# TeensyCtrlr.net
KiCad netlist of a schematic drawn in EAGLE
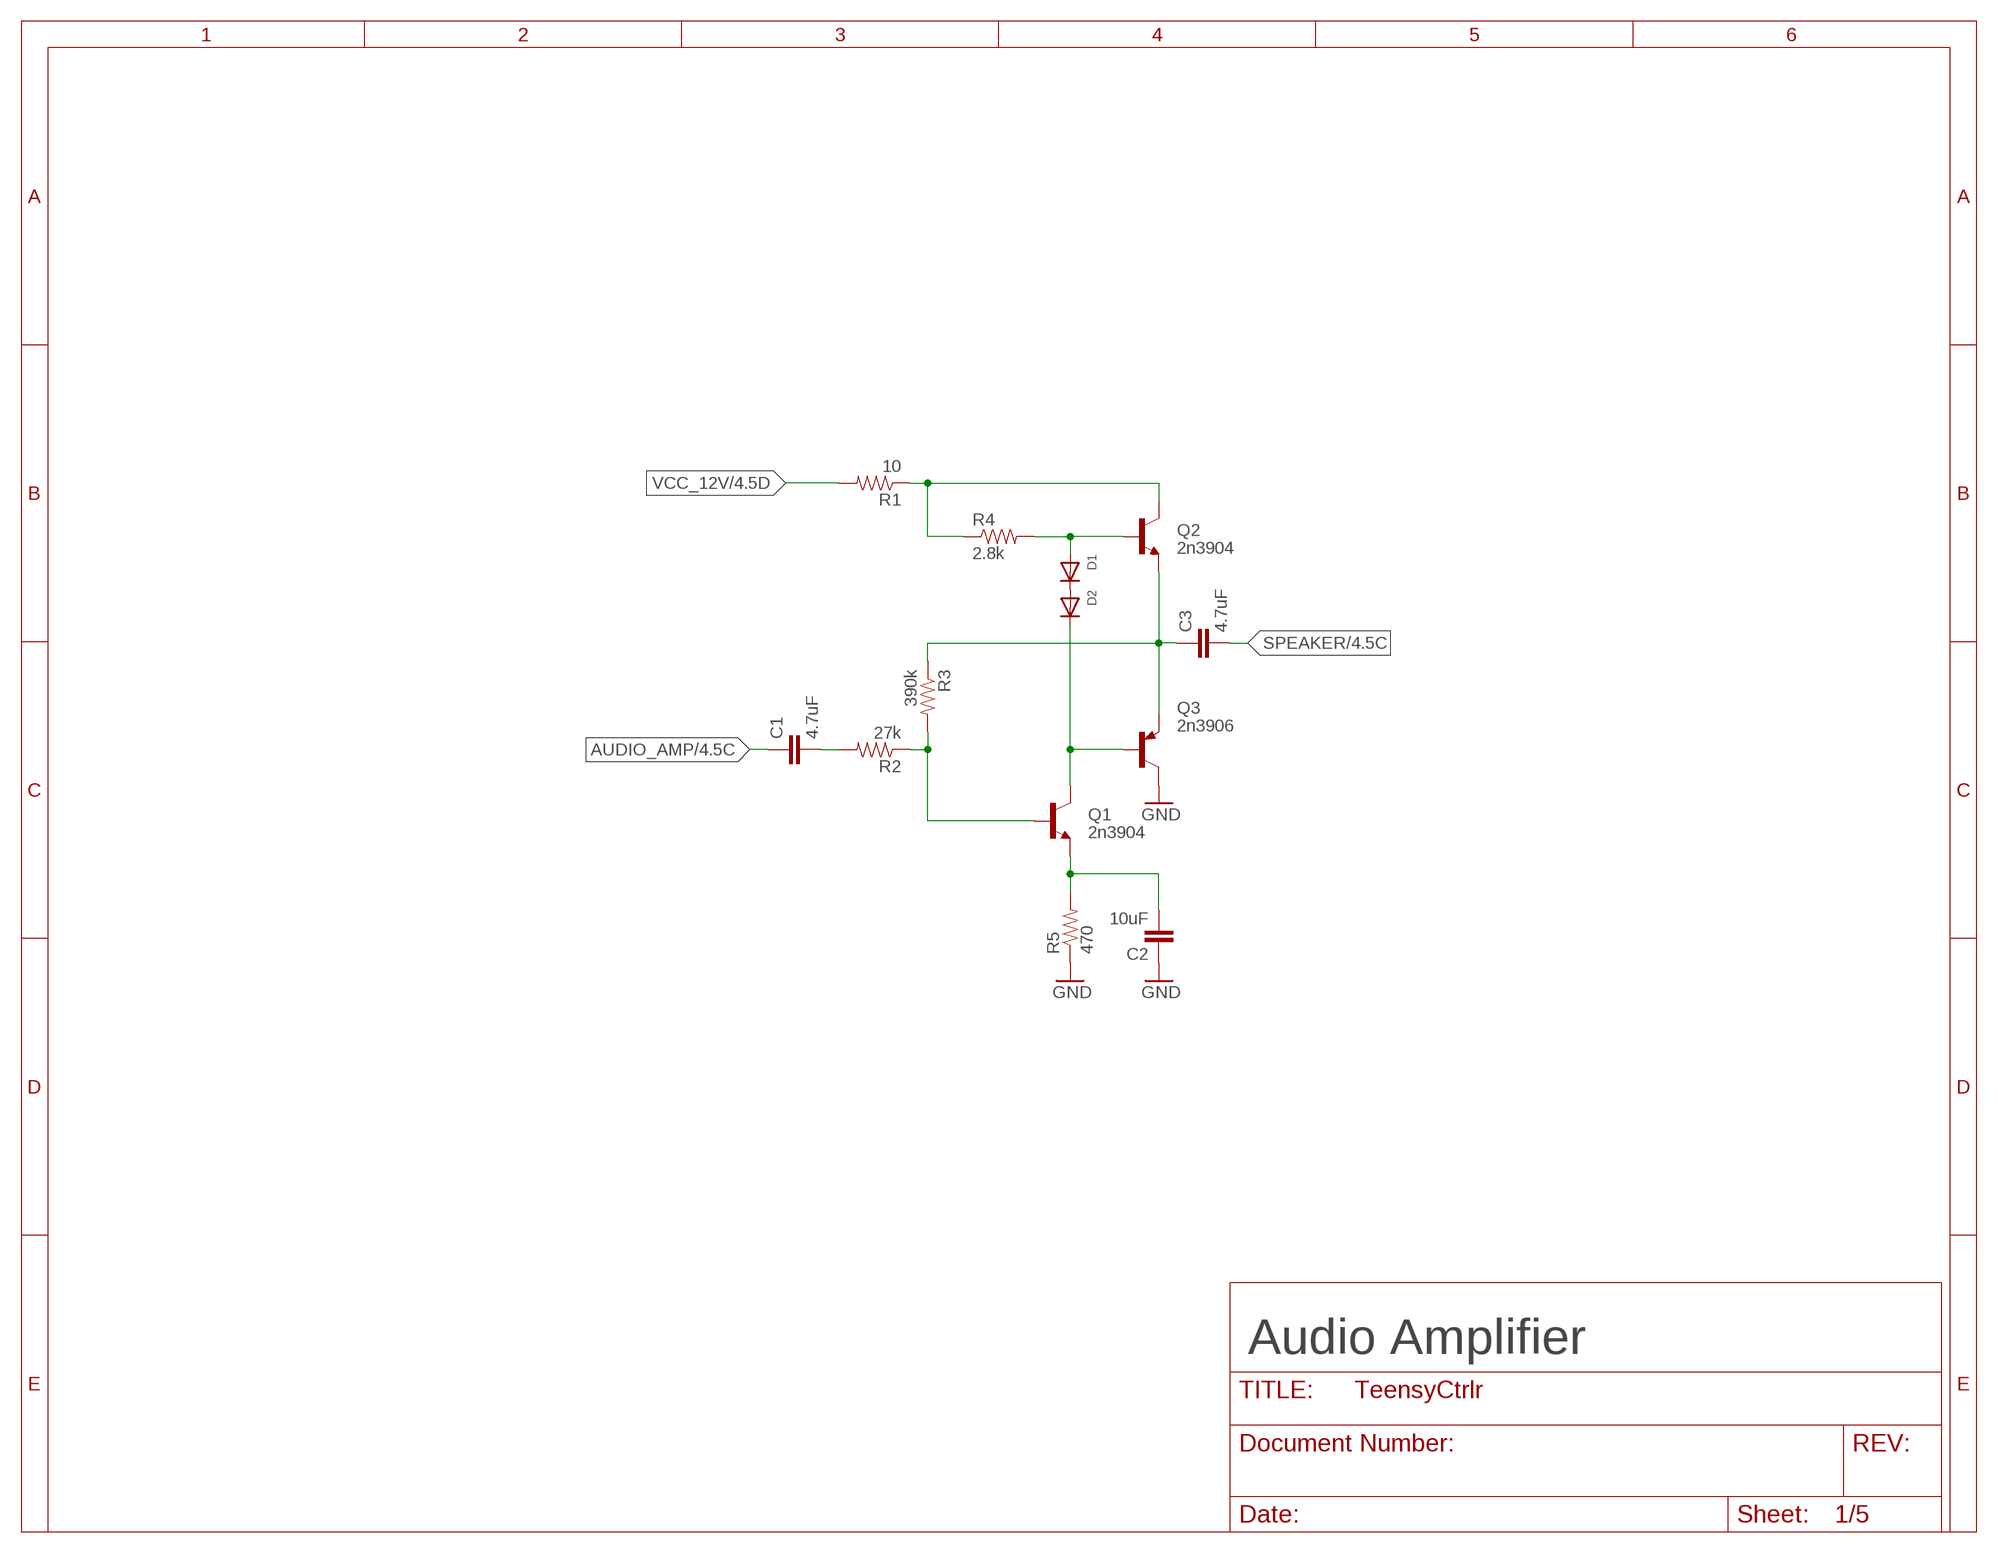
[diagram p0: schematic, sheet 1]
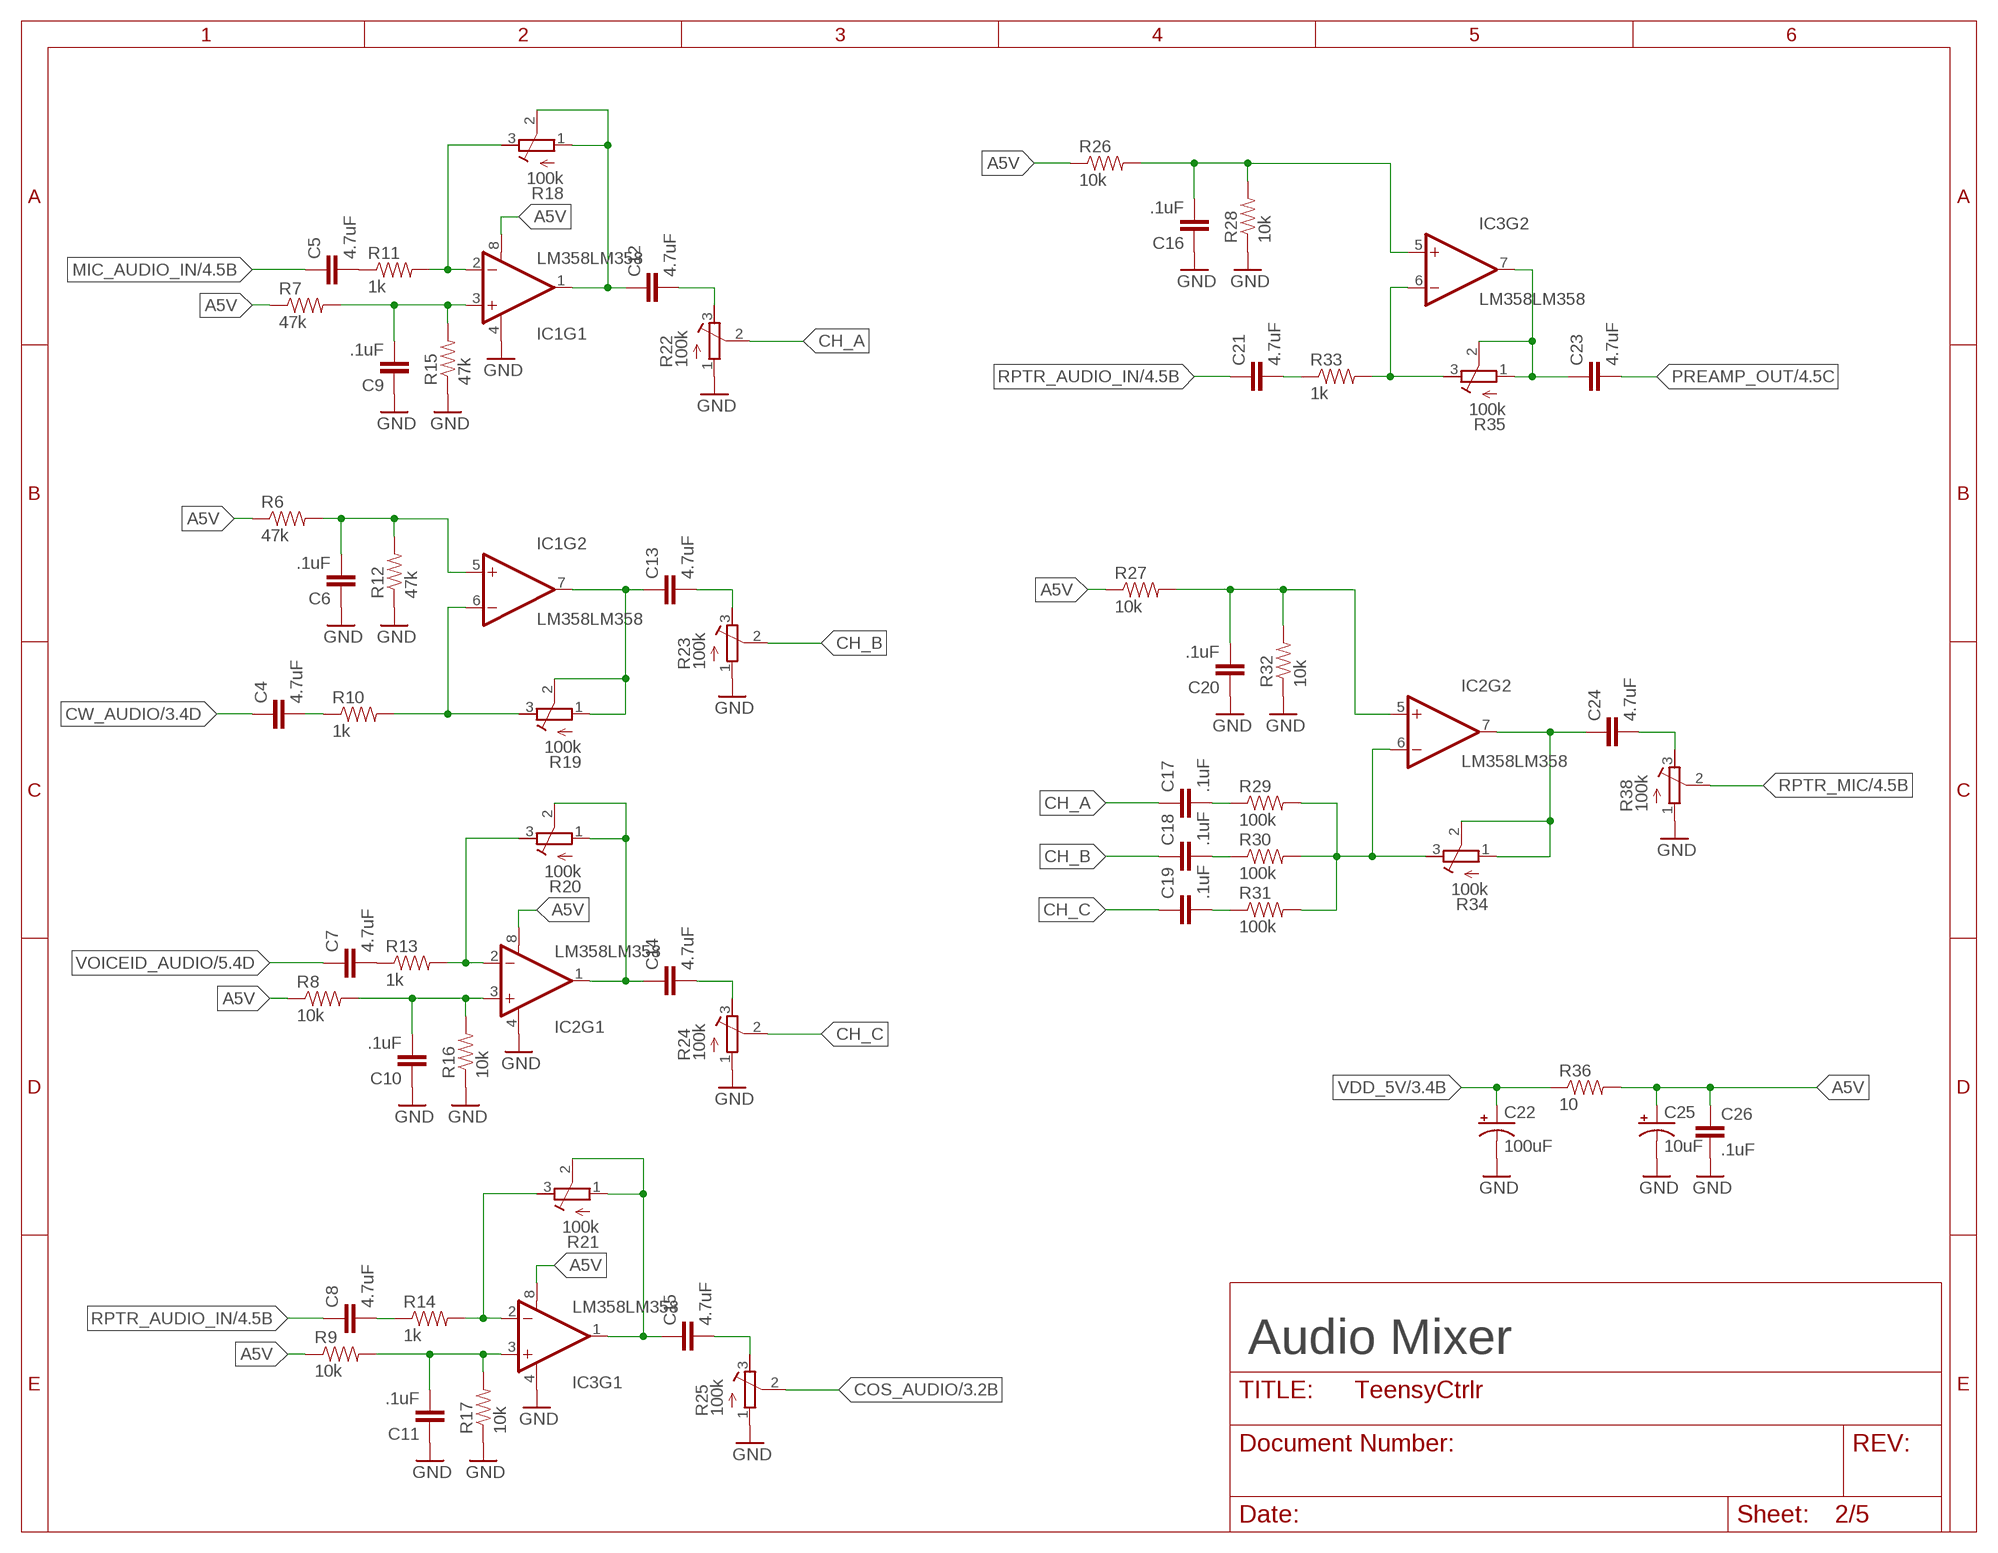
[diagram p1: schematic, sheet 2]
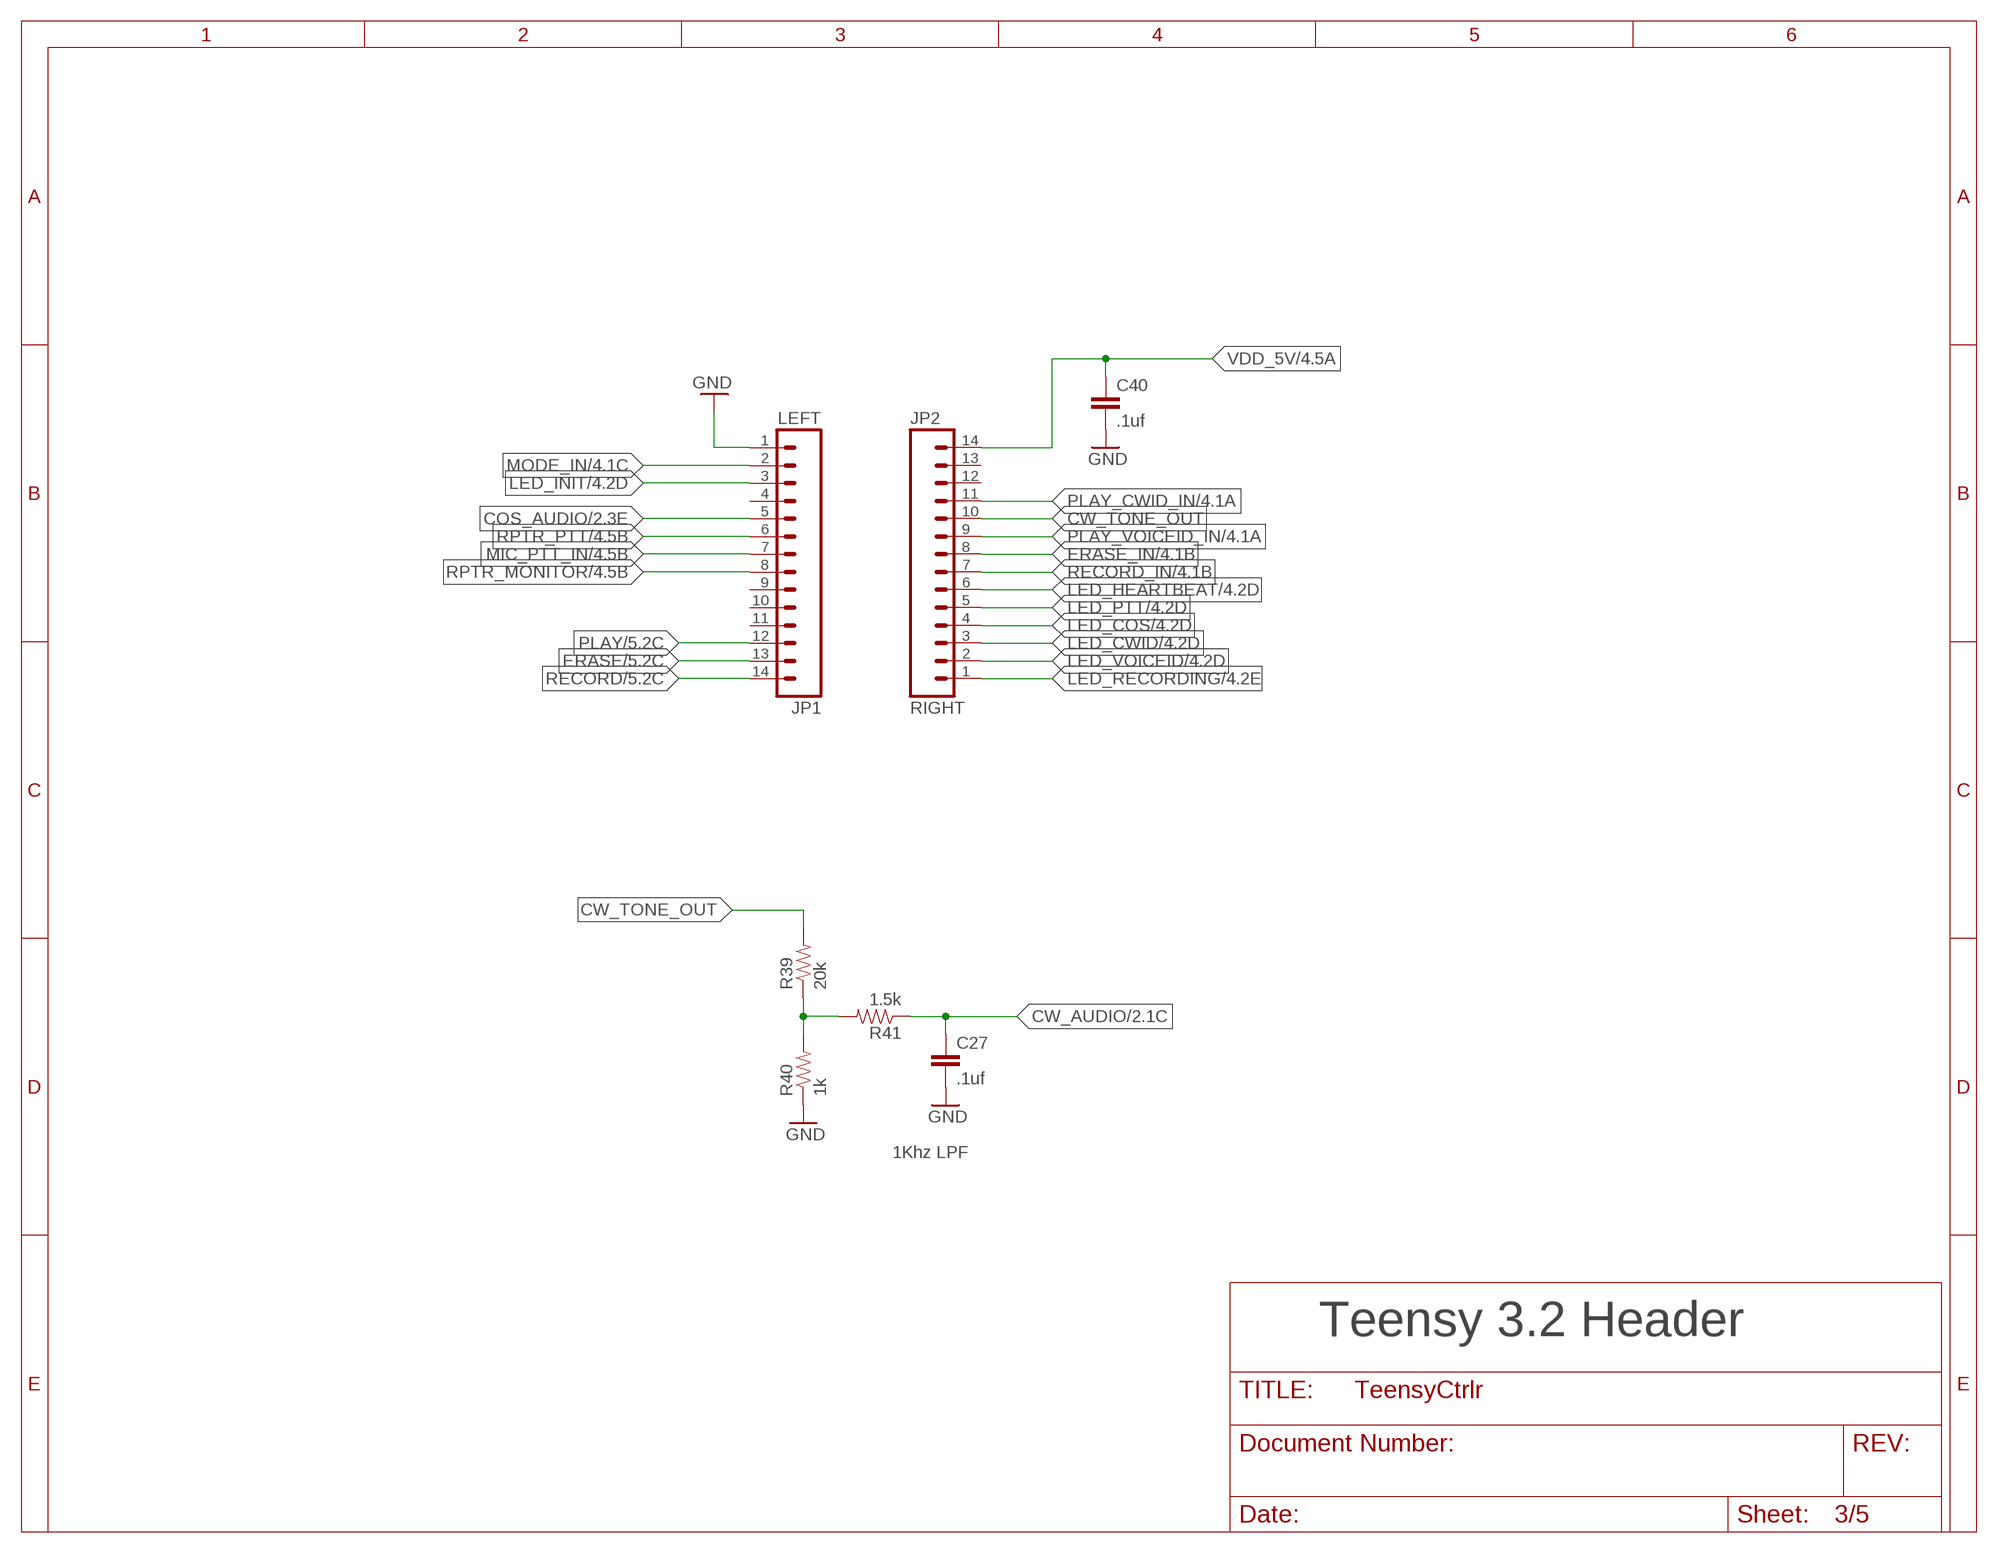
[diagram p2: schematic, sheet 3]
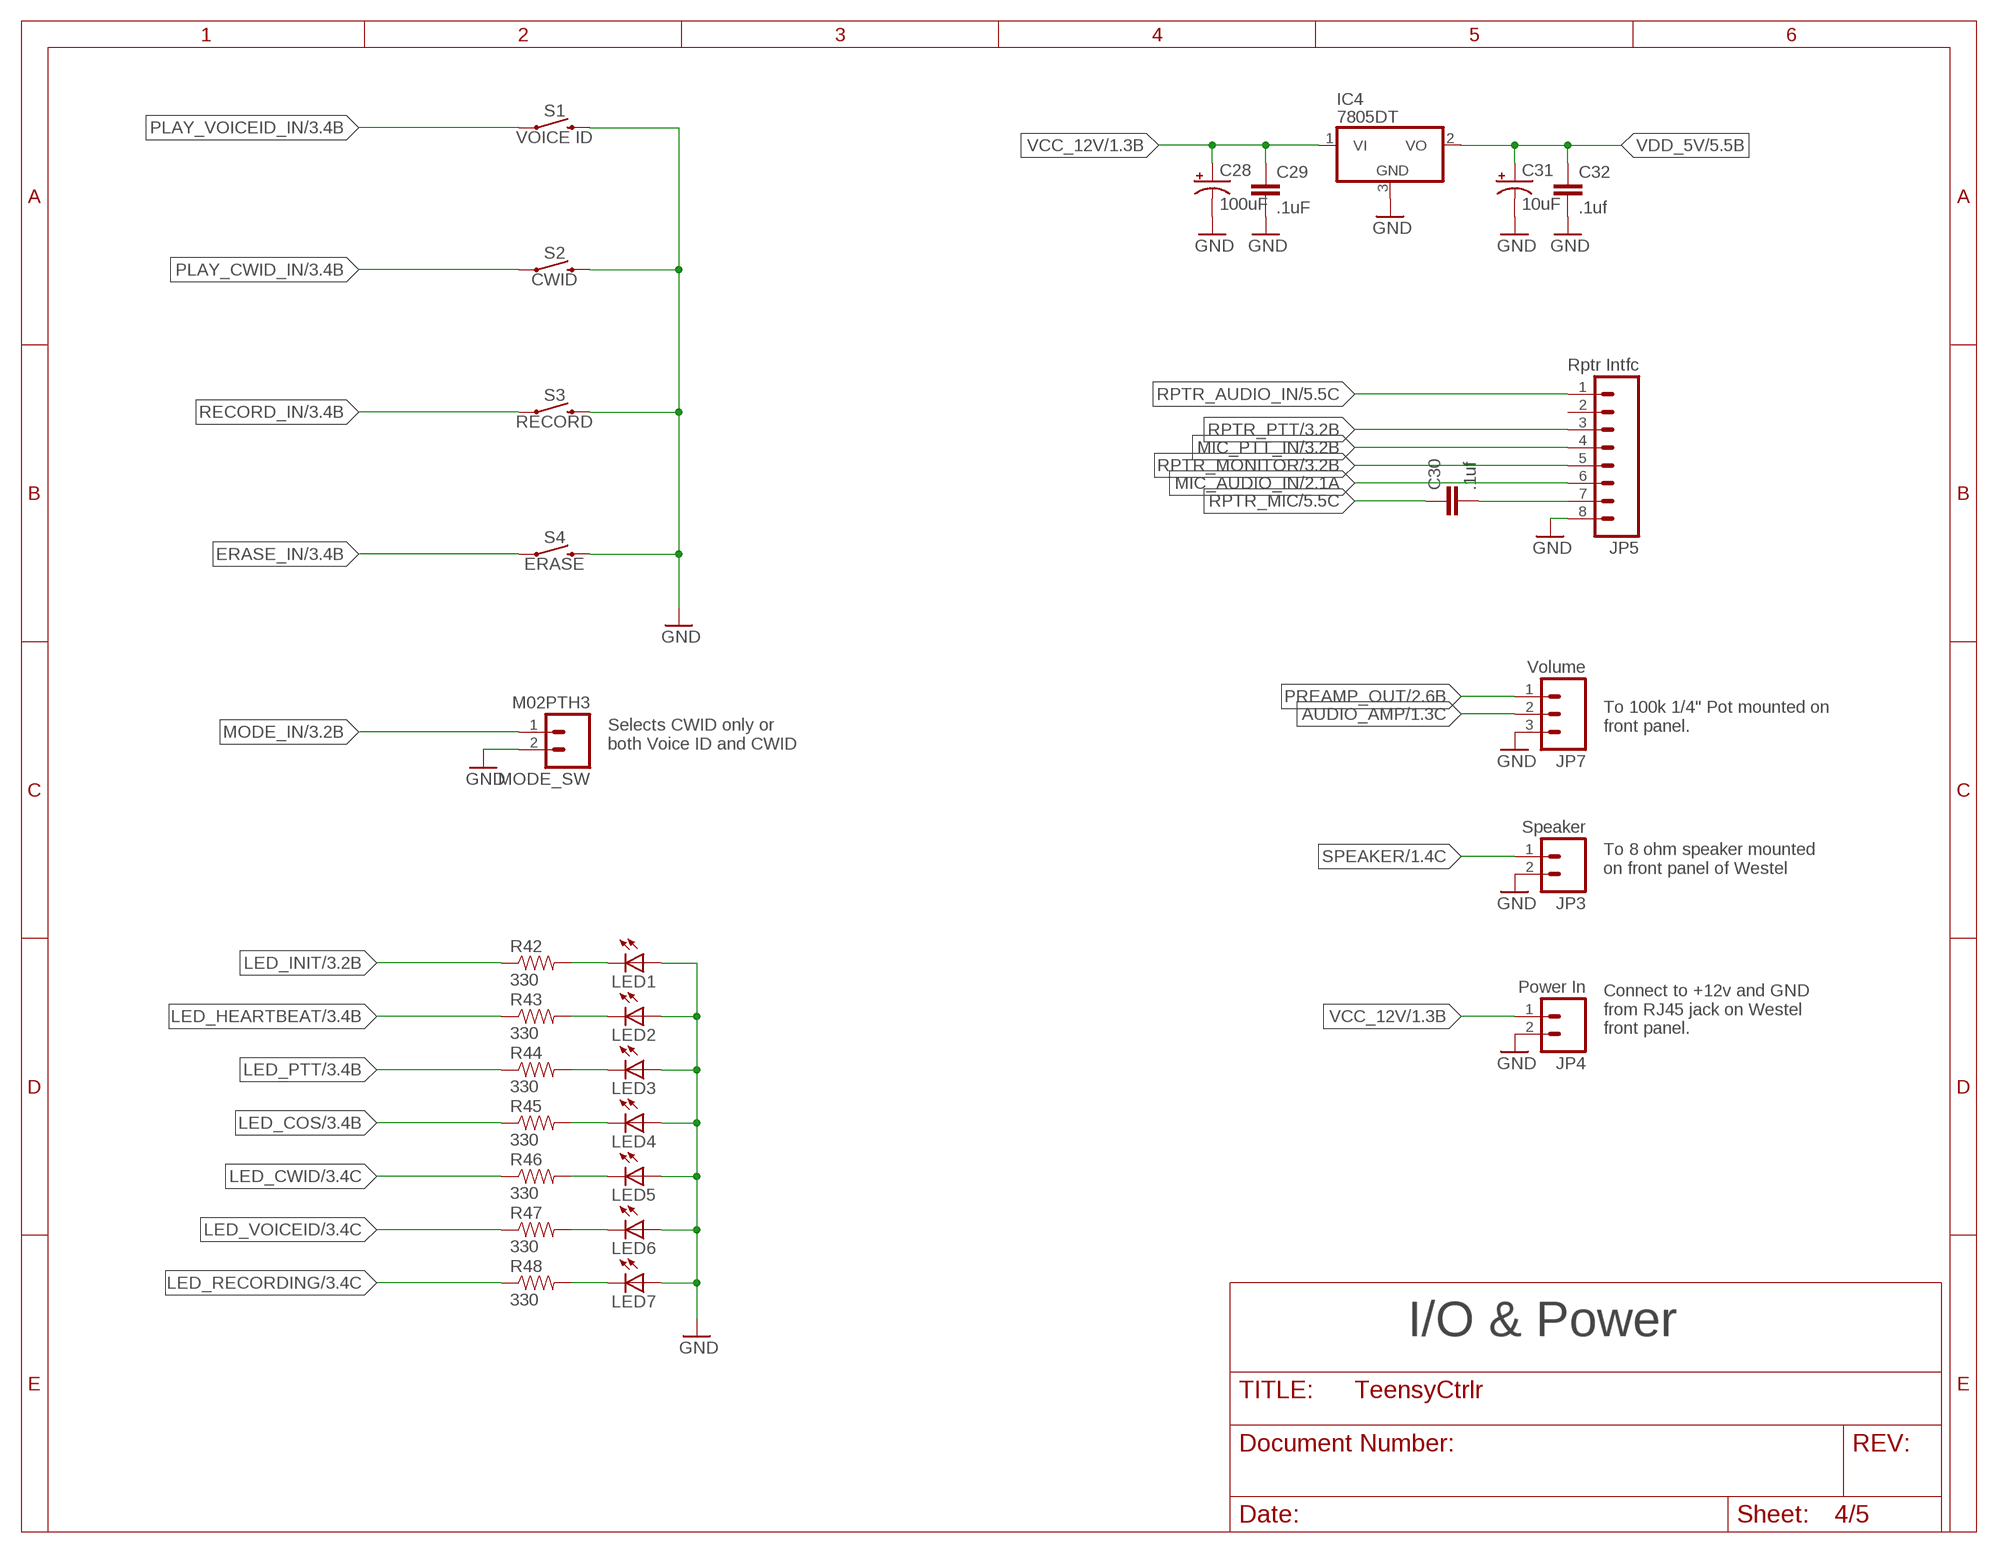
[diagram p3: schematic, sheet 4]
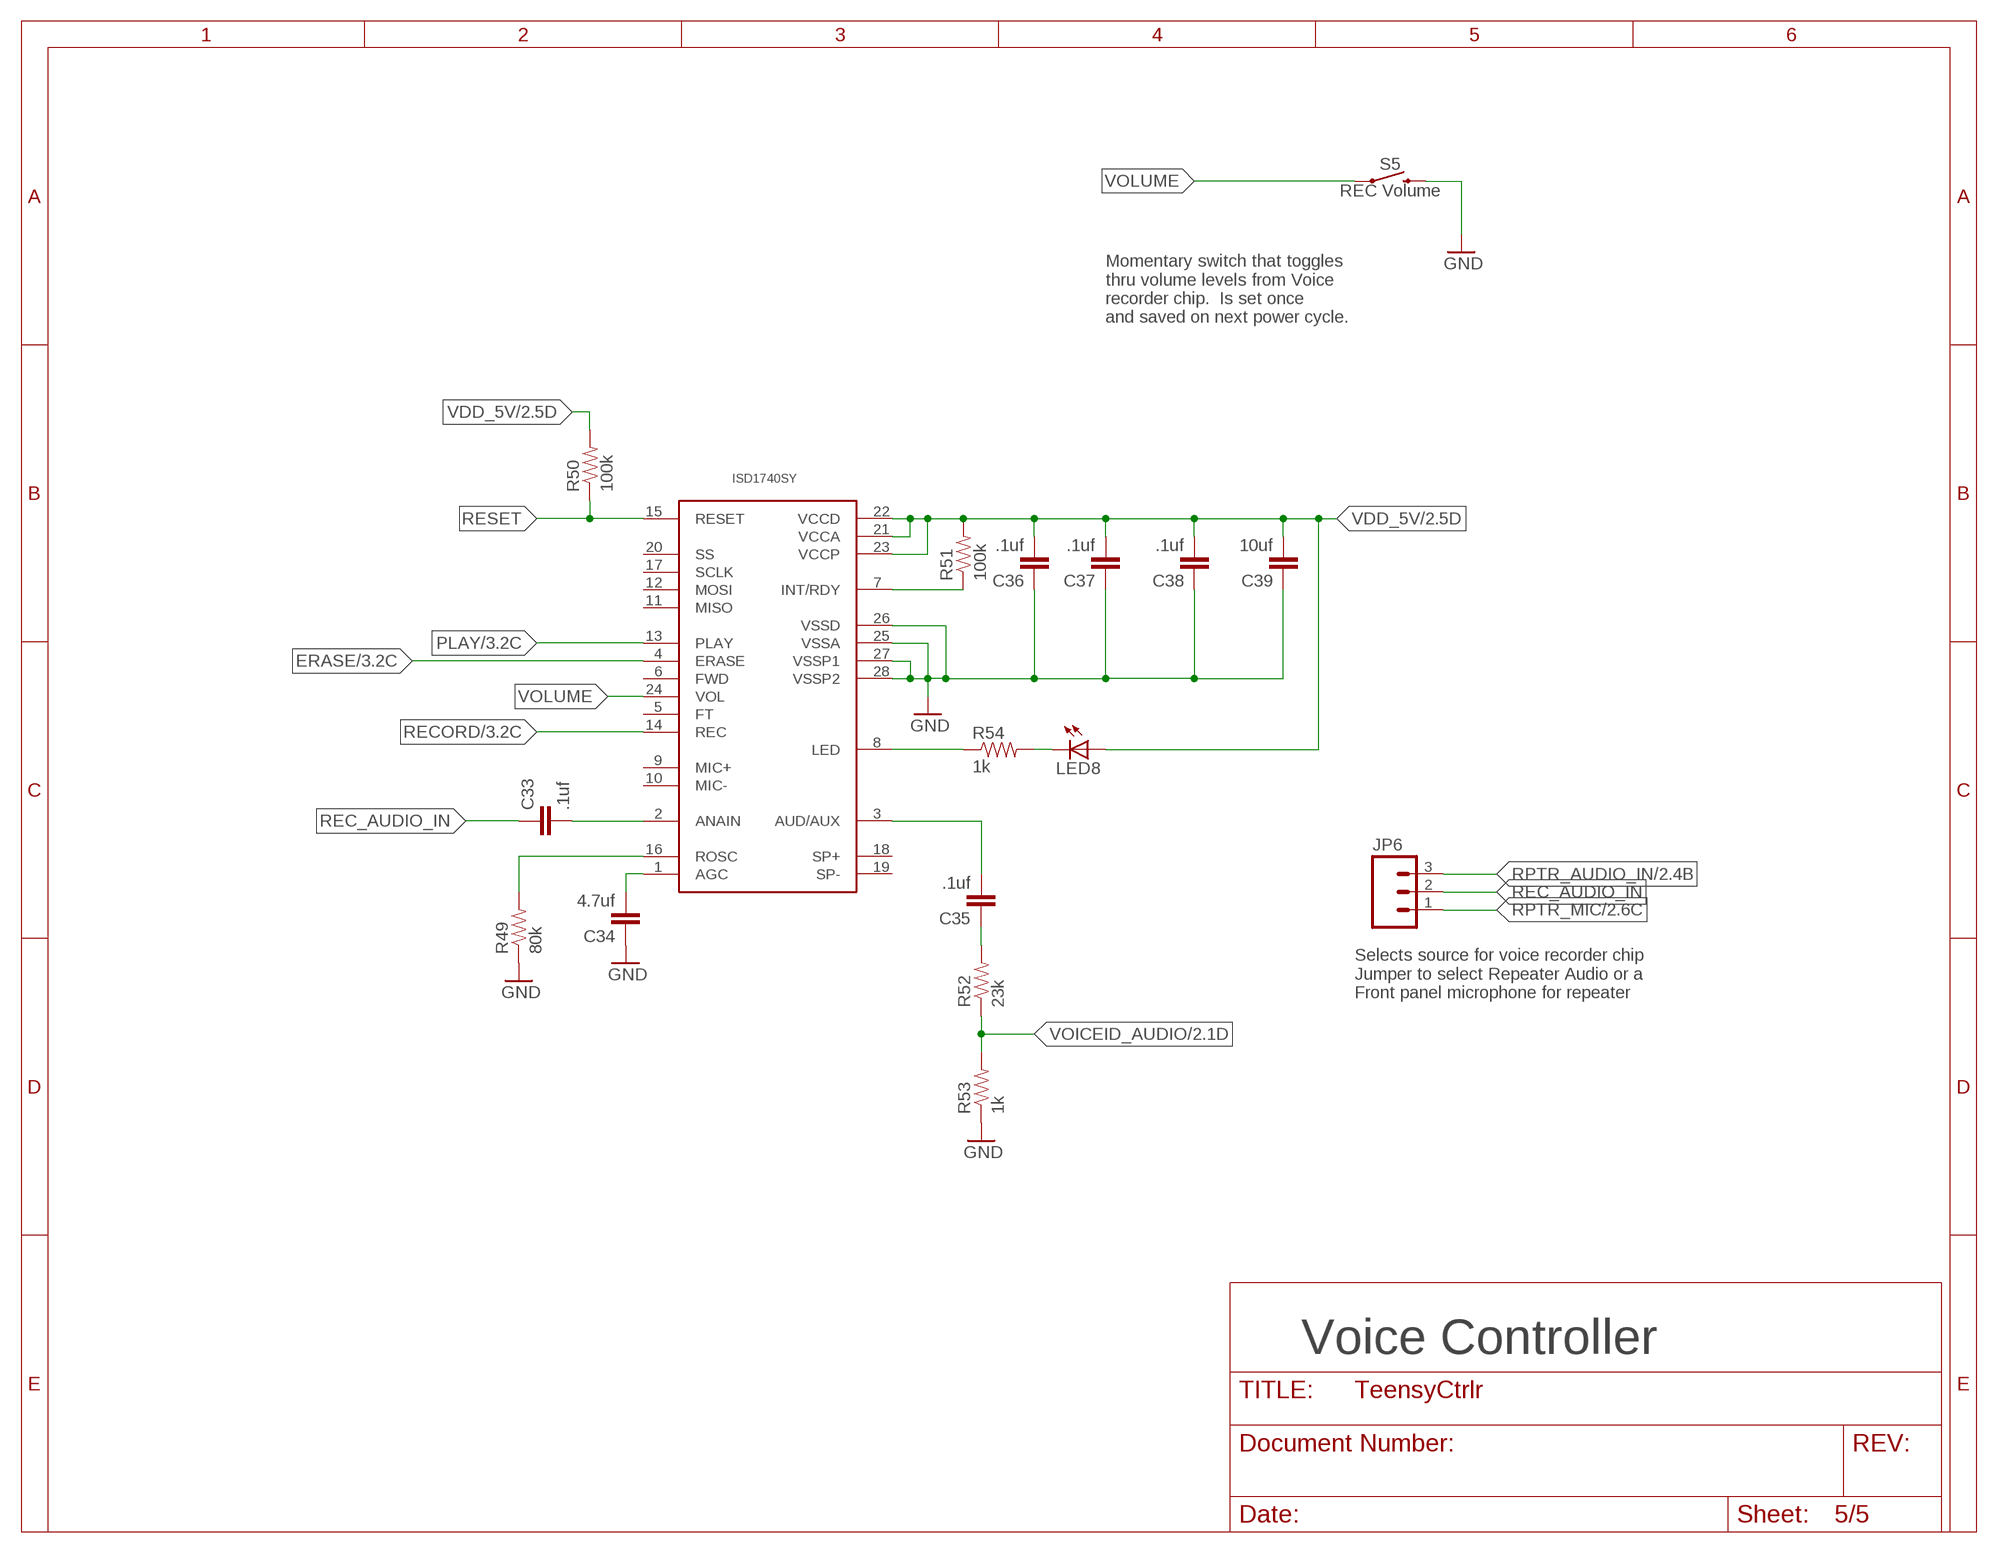
[diagram p4: schematic, sheet 5]

(export (version "E")
  (design (tool "Eeschema 10.0.6"))
  (components
    (comp (ref "C28")
      (value "100uF")
      (footprint "eagle-import:CPOL-RADIAL-1000UF-25V")
      (libsource (lib "eagle-import") (part "CAP_POLPTH4"))
    )
    (comp (ref "C29")
      (value ".1uF")
      (footprint "eagle-import:0805")
      (libsource (lib "eagle-import") (part "CAP0805"))
    )
    (comp (ref "C30")
      (value ".1uf")
      (footprint "eagle-import:0805")
      (libsource (lib "eagle-import") (part "CAP0805"))
    )
    (comp (ref "C31")
      (value "10uF")
      (footprint "eagle-import:CPOL-RADIAL-100UF-25V")
      (libsource (lib "eagle-import") (part "CAP_POLPTH1"))
    )
    (comp (ref "C32")
      (value ".1uf")
      (footprint "eagle-import:0805")
      (libsource (lib "eagle-import") (part "CAP0805"))
    )
    (comp (ref "IC4")
      (value "7805DT")
      (footprint "eagle-import:TO252")
      (libsource (lib "eagle-import") (part "78DT05"))
    )
    (comp (ref "JP3")
      (value "Speaker")
      (footprint "eagle-import:1X02_LONGPADS")
      (libsource (lib "eagle-import") (part "M02PTH3"))
    )
    (comp (ref "JP4")
      (value "Power In")
      (footprint "eagle-import:1X02_LONGPADS")
      (libsource (lib "eagle-import") (part "M02PTH3"))
    )
    (comp (ref "JP5")
      (value "Rptr Intfc")
      (footprint "eagle-import:1X08_LONGPADS")
      (libsource (lib "eagle-import") (part "M08LONGPADS"))
    )
    (comp (ref "JP7")
      (value "Volume")
      (footprint "eagle-import:1X03_LONGPADS")
      (libsource (lib "eagle-import") (part "M03LONGPADS"))
    )
    (comp (ref "LED1")
      (value "LED5MM")
      (footprint "eagle-import:LED5MM")
      (libsource (lib "eagle-import") (part "LED5MM"))
    )
    (comp (ref "LED2")
      (value "LED5MM")
      (footprint "eagle-import:LED5MM")
      (libsource (lib "eagle-import") (part "LED5MM"))
    )
    (comp (ref "LED3")
      (value "LED5MM")
      (footprint "eagle-import:LED5MM")
      (libsource (lib "eagle-import") (part "LED5MM"))
    )
    (comp (ref "LED4")
      (value "LED5MM")
      (footprint "eagle-import:LED5MM")
      (libsource (lib "eagle-import") (part "LED5MM"))
    )
    (comp (ref "LED5")
      (value "LED5MM")
      (footprint "eagle-import:LED5MM")
      (libsource (lib "eagle-import") (part "LED5MM"))
    )
    (comp (ref "LED6")
      (value "LED5MM")
      (footprint "eagle-import:LED5MM")
      (libsource (lib "eagle-import") (part "LED5MM"))
    )
    (comp (ref "LED7")
      (value "LED5MM")
      (footprint "eagle-import:LED5MM")
      (libsource (lib "eagle-import") (part "LED5MM"))
    )
    (comp (ref "MODE_SW")
      (value "M02PTH3")
      (footprint "eagle-import:1X02_LONGPADS")
      (libsource (lib "eagle-import") (part "M02PTH3"))
    )
    (comp (ref "R42")
      (value "330")
      (footprint "eagle-import:0805")
      (libsource (lib "eagle-import") (part "RESISTOR0805-RES"))
    )
    (comp (ref "R43")
      (value "330")
      (footprint "eagle-import:0805")
      (libsource (lib "eagle-import") (part "RESISTOR0805-RES"))
    )
    (comp (ref "R44")
      (value "330")
      (footprint "eagle-import:0805")
      (libsource (lib "eagle-import") (part "RESISTOR0805-RES"))
    )
    (comp (ref "R45")
      (value "330")
      (footprint "eagle-import:0805")
      (libsource (lib "eagle-import") (part "RESISTOR0805-RES"))
    )
    (comp (ref "R46")
      (value "330")
      (footprint "eagle-import:0805")
      (libsource (lib "eagle-import") (part "RESISTOR0805-RES"))
    )
    (comp (ref "R47")
      (value "330")
      (footprint "eagle-import:0805")
      (libsource (lib "eagle-import") (part "RESISTOR0805-RES"))
    )
    (comp (ref "R48")
      (value "330")
      (footprint "eagle-import:0805")
      (libsource (lib "eagle-import") (part "RESISTOR0805-RES"))
    )
    (comp (ref "S1")
      (value "VOICE ID")
      (footprint "eagle-import:TACTILE_SWITCH_PTH_6.0MM")
      (libsource (lib "eagle-import") (part "MOMENTARY-SWITCH-SPST-PTH-6.0MM"))
    )
    (comp (ref "S2")
      (value "CWID")
      (footprint "eagle-import:TACTILE_SWITCH_PTH_6.0MM")
      (libsource (lib "eagle-import") (part "MOMENTARY-SWITCH-SPST-PTH-6.0MM"))
    )
    (comp (ref "S3")
      (value "RECORD")
      (footprint "eagle-import:TACTILE_SWITCH_PTH_6.0MM")
      (libsource (lib "eagle-import") (part "MOMENTARY-SWITCH-SPST-PTH-6.0MM"))
    )
    (comp (ref "S4")
      (value "ERASE")
      (footprint "eagle-import:TACTILE_SWITCH_PTH_6.0MM")
      (libsource (lib "eagle-import") (part "MOMENTARY-SWITCH-SPST-PTH-6.0MM"))
    )
    (comp (ref "C1")
      (value "4.7uF")
      (footprint "eagle-import:CAP-PTH-SMALL")
      (libsource (lib "eagle-import") (part "CAPPTH"))
    )
    (comp (ref "C2")
      (value "10uF")
      (footprint "eagle-import:CAP-PTH-SMALL")
      (libsource (lib "eagle-import") (part "CAPPTH"))
    )
    (comp (ref "C3")
      (value "4.7uF")
      (footprint "eagle-import:CAP-PTH-SMALL")
      (libsource (lib "eagle-import") (part "CAPPTH"))
    )
    (comp (ref "D1")
      (value "DIODEDO-1N4148")
      (footprint "eagle-import:DO-1N4148")
      (libsource (lib "eagle-import") (part "DIODEDO-1N4148"))
    )
    (comp (ref "D2")
      (value "DIODEDO-1N4148")
      (footprint "eagle-import:DO-1N4148")
      (libsource (lib "eagle-import") (part "DIODEDO-1N4148"))
    )
    (comp (ref "Q1")
      (value "2n3904")
      (footprint "eagle-import:TO-92-AMMO")
      (libsource (lib "eagle-import") (part "TRANSISTOR_NPNTO-92-AMMO"))
    )
    (comp (ref "Q2")
      (value "2n3904")
      (footprint "eagle-import:TO-92-AMMO")
      (libsource (lib "eagle-import") (part "TRANSISTOR_NPNTO-92-AMMO"))
    )
    (comp (ref "Q3")
      (value "2n3906")
      (footprint "eagle-import:TO92-EBC")
      (libsource (lib "eagle-import") (part "-PNP-TO92-EBCBC328-25"))
    )
    (comp (ref "R1")
      (value "10")
      (footprint "eagle-import:0805")
      (libsource (lib "eagle-import") (part "RESISTOR0805-RES"))
    )
    (comp (ref "R2")
      (value "27k")
      (footprint "eagle-import:0805")
      (libsource (lib "eagle-import") (part "RESISTOR0805-RES"))
    )
    (comp (ref "R3")
      (value "390k")
      (footprint "eagle-import:0805")
      (libsource (lib "eagle-import") (part "RESISTOR0805-RES"))
    )
    (comp (ref "R4")
      (value "2.8k")
      (footprint "eagle-import:0805")
      (libsource (lib "eagle-import") (part "RESISTOR0805-RES"))
    )
    (comp (ref "R5")
      (value "470")
      (footprint "eagle-import:0805")
      (libsource (lib "eagle-import") (part "RESISTOR0805-RES"))
    )
    (comp (ref "C33")
      (value ".1uf")
      (footprint "eagle-import:0805")
      (libsource (lib "eagle-import") (part "CAP0805"))
    )
    (comp (ref "C34")
      (value "4.7uf")
      (footprint "eagle-import:0805")
      (libsource (lib "eagle-import") (part "CAP0805"))
    )
    (comp (ref "C35")
      (value ".1uf")
      (footprint "eagle-import:0805")
      (libsource (lib "eagle-import") (part "CAP0805"))
    )
    (comp (ref "C36")
      (value ".1uf")
      (footprint "eagle-import:0805")
      (libsource (lib "eagle-import") (part "CAP0805"))
    )
    (comp (ref "C37")
      (value ".1uf")
      (footprint "eagle-import:0805")
      (libsource (lib "eagle-import") (part "CAP0805"))
    )
    (comp (ref "C38")
      (value ".1uf")
      (footprint "eagle-import:0805")
      (libsource (lib "eagle-import") (part "CAP0805"))
    )
    (comp (ref "C39")
      (value "10uf")
      (footprint "eagle-import:0805")
      (libsource (lib "eagle-import") (part "CAP0805"))
    )
    (comp (ref "IC$1")
      (value "ISD1740SYSOIC28")
      (footprint "eagle-import:SOIC-28")
      (libsource (lib "eagle-import") (part "ISD1740SYSOIC28"))
    )
    (comp (ref "JP6")
      (value "M03LONGPADS")
      (footprint "eagle-import:1X03_LONGPADS")
      (libsource (lib "eagle-import") (part "M03LONGPADS"))
    )
    (comp (ref "LED8")
      (value "LEDCHIP-LED0805")
      (footprint "eagle-import:CHIP-LED0805")
      (libsource (lib "eagle-import") (part "LEDCHIP-LED0805"))
    )
    (comp (ref "R49")
      (value "80k")
      (footprint "eagle-import:0805")
      (libsource (lib "eagle-import") (part "RESISTOR0805-RES"))
    )
    (comp (ref "R50")
      (value "100k")
      (footprint "eagle-import:0805")
      (libsource (lib "eagle-import") (part "RESISTOR0805-RES"))
    )
    (comp (ref "R51")
      (value "100k")
      (footprint "eagle-import:0805")
      (libsource (lib "eagle-import") (part "RESISTOR0805-RES"))
    )
    (comp (ref "R52")
      (value "23k")
      (footprint "eagle-import:0805")
      (libsource (lib "eagle-import") (part "RESISTOR0805-RES"))
    )
    (comp (ref "R53")
      (value "1k")
      (footprint "eagle-import:0805")
      (libsource (lib "eagle-import") (part "RESISTOR0805-RES"))
    )
    (comp (ref "R54")
      (value "1k")
      (footprint "eagle-import:0805")
      (libsource (lib "eagle-import") (part "RESISTOR0805-RES"))
    )
    (comp (ref "S5")
      (value "REC Volume")
      (footprint "eagle-import:TACTILE_SWITCH_PTH_6.0MM")
      (libsource (lib "eagle-import") (part "MOMENTARY-SWITCH-SPST-PTH-6.0MM"))
    )
    (comp (ref "C27")
      (value ".1uf")
      (footprint "eagle-import:0805")
      (libsource (lib "eagle-import") (part "CAP0805"))
    )
    (comp (ref "C40")
      (value ".1uf")
      (footprint "eagle-import:0805")
      (libsource (lib "eagle-import") (part "CAP0805"))
    )
    (comp (ref "JP1")
      (value "LEFT")
      (footprint "eagle-import:1X14-LONGPADS")
      (libsource (lib "eagle-import") (part "M14LONGPADS"))
    )
    (comp (ref "JP2")
      (value "RIGHT")
      (footprint "eagle-import:1X14-LONGPADS")
      (libsource (lib "eagle-import") (part "M14LONGPADS"))
    )
    (comp (ref "R39")
      (value "20k")
      (footprint "eagle-import:0805")
      (libsource (lib "eagle-import") (part "RESISTOR0805-RES"))
    )
    (comp (ref "R40")
      (value "1k")
      (footprint "eagle-import:0805")
      (libsource (lib "eagle-import") (part "RESISTOR0805-RES"))
    )
    (comp (ref "R41")
      (value "1.5k")
      (footprint "eagle-import:0805")
      (libsource (lib "eagle-import") (part "RESISTOR0805-RES"))
    )
    (comp (ref "C4")
      (value "4.7uF")
      (footprint "eagle-import:CAP-PTH-SMALL2")
      (libsource (lib "eagle-import") (part "CAPPTH2"))
    )
    (comp (ref "C5")
      (value "4.7uF")
      (footprint "eagle-import:CAP-PTH-SMALL2")
      (libsource (lib "eagle-import") (part "CAPPTH2"))
    )
    (comp (ref "C6")
      (value ".1uF")
      (footprint "eagle-import:0805")
      (libsource (lib "eagle-import") (part "CAP0805"))
    )
    (comp (ref "C7")
      (value "4.7uF")
      (footprint "eagle-import:CAP-PTH-SMALL2")
      (libsource (lib "eagle-import") (part "CAPPTH2"))
    )
    (comp (ref "C8")
      (value "4.7uF")
      (footprint "eagle-import:CAP-PTH-SMALL2")
      (libsource (lib "eagle-import") (part "CAPPTH2"))
    )
    (comp (ref "C9")
      (value ".1uF")
      (footprint "eagle-import:0805")
      (libsource (lib "eagle-import") (part "CAP0805"))
    )
    (comp (ref "C10")
      (value ".1uF")
      (footprint "eagle-import:0805")
      (libsource (lib "eagle-import") (part "CAP0805"))
    )
    (comp (ref "C11")
      (value ".1uF")
      (footprint "eagle-import:0805")
      (libsource (lib "eagle-import") (part "CAP0805"))
    )
    (comp (ref "C12")
      (value "4.7uF")
      (footprint "eagle-import:CAP-PTH-SMALL2")
      (libsource (lib "eagle-import") (part "CAPPTH2"))
    )
    (comp (ref "C13")
      (value "4.7uF")
      (footprint "eagle-import:CAP-PTH-SMALL2")
      (libsource (lib "eagle-import") (part "CAPPTH2"))
    )
    (comp (ref "C14")
      (value "4.7uF")
      (footprint "eagle-import:CAP-PTH-SMALL2")
      (libsource (lib "eagle-import") (part "CAPPTH2"))
    )
    (comp (ref "C15")
      (value "4.7uF")
      (footprint "eagle-import:CAP-PTH-SMALL2")
      (libsource (lib "eagle-import") (part "CAPPTH2"))
    )
    (comp (ref "C16")
      (value ".1uF")
      (footprint "eagle-import:0805")
      (libsource (lib "eagle-import") (part "CAP0805"))
    )
    (comp (ref "C17")
      (value ".1uF")
      (footprint "eagle-import:0805")
      (libsource (lib "eagle-import") (part "CAP0805"))
    )
    (comp (ref "C18")
      (value ".1uF")
      (footprint "eagle-import:0805")
      (libsource (lib "eagle-import") (part "CAP0805"))
    )
    (comp (ref "C19")
      (value ".1uF")
      (footprint "eagle-import:0805")
      (libsource (lib "eagle-import") (part "CAP0805"))
    )
    (comp (ref "C20")
      (value ".1uF")
      (footprint "eagle-import:0805")
      (libsource (lib "eagle-import") (part "CAP0805"))
    )
    (comp (ref "C21")
      (value "4.7uF")
      (footprint "eagle-import:CAP-PTH-SMALL2")
      (libsource (lib "eagle-import") (part "CAPPTH2"))
    )
    (comp (ref "C22")
      (value "100uF")
      (footprint "eagle-import:CPOL-RADIAL-10UF-25V")
      (libsource (lib "eagle-import") (part "CAP_POLPTH2"))
    )
    (comp (ref "C23")
      (value "4.7uF")
      (footprint "eagle-import:CAP-PTH-SMALL2")
      (libsource (lib "eagle-import") (part "CAPPTH2"))
    )
    (comp (ref "C24")
      (value "4.7uF")
      (footprint "eagle-import:CAP-PTH-SMALL2")
      (libsource (lib "eagle-import") (part "CAPPTH2"))
    )
    (comp (ref "C25")
      (value "10uF")
      (footprint "eagle-import:CPOL-RADIAL-100UF-25V")
      (libsource (lib "eagle-import") (part "CAP_POLPTH1"))
    )
    (comp (ref "C26")
      (value ".1uF")
      (footprint "eagle-import:0805")
      (libsource (lib "eagle-import") (part "CAP0805"))
    )
    (comp (ref "IC1")
      (value "LM358LM358")
      (footprint "eagle-import:SOIC8")
      (libsource (lib "eagle-import") (part "LM358LM358"))
    )
    (comp (ref "IC2")
      (value "LM358LM358")
      (footprint "eagle-import:SOIC8")
      (libsource (lib "eagle-import") (part "LM358LM358"))
    )
    (comp (ref "IC3")
      (value "LM358LM358")
      (footprint "eagle-import:SOIC8")
      (libsource (lib "eagle-import") (part "LM358LM358"))
    )
    (comp (ref "R6")
      (value "47k")
      (footprint "eagle-import:0805")
      (libsource (lib "eagle-import") (part "RESISTOR0805-RES"))
    )
    (comp (ref "R7")
      (value "47k")
      (footprint "eagle-import:0805")
      (libsource (lib "eagle-import") (part "RESISTOR0805-RES"))
    )
    (comp (ref "R8")
      (value "10k")
      (footprint "eagle-import:0805")
      (libsource (lib "eagle-import") (part "RESISTOR0805-RES"))
    )
    (comp (ref "R9")
      (value "10k")
      (footprint "eagle-import:0805")
      (libsource (lib "eagle-import") (part "RESISTOR0805-RES"))
    )
    (comp (ref "R10")
      (value "1k")
      (footprint "eagle-import:0805")
      (libsource (lib "eagle-import") (part "RESISTOR0805-RES"))
    )
    (comp (ref "R11")
      (value "1k")
      (footprint "eagle-import:0805")
      (libsource (lib "eagle-import") (part "RESISTOR0805-RES"))
    )
    (comp (ref "R12")
      (value "47k")
      (footprint "eagle-import:0805")
      (libsource (lib "eagle-import") (part "RESISTOR0805-RES"))
    )
    (comp (ref "R13")
      (value "1k")
      (footprint "eagle-import:0805")
      (libsource (lib "eagle-import") (part "RESISTOR0805-RES"))
    )
    (comp (ref "R14")
      (value "1k")
      (footprint "eagle-import:0805")
      (libsource (lib "eagle-import") (part "RESISTOR0805-RES"))
    )
    (comp (ref "R15")
      (value "47k")
      (footprint "eagle-import:0805")
      (libsource (lib "eagle-import") (part "RESISTOR0805-RES"))
    )
    (comp (ref "R16")
      (value "10k")
      (footprint "eagle-import:0805")
      (libsource (lib "eagle-import") (part "RESISTOR0805-RES"))
    )
    (comp (ref "R17")
      (value "10k")
      (footprint "eagle-import:0805")
      (libsource (lib "eagle-import") (part "RESISTOR0805-RES"))
    )
    (comp (ref "R18")
      (value "100k")
      (footprint "eagle-import:RTRIM3296X")
      (libsource (lib "eagle-import") (part "R-TRIMM3296X"))
    )
    (comp (ref "R19")
      (value "100k")
      (footprint "eagle-import:RTRIM3296X")
      (libsource (lib "eagle-import") (part "R-TRIMM3296X"))
    )
    (comp (ref "R20")
      (value "100k")
      (footprint "eagle-import:RTRIM3296X")
      (libsource (lib "eagle-import") (part "R-TRIMM3296X"))
    )
    (comp (ref "R21")
      (value "100k")
      (footprint "eagle-import:RTRIM3296X")
      (libsource (lib "eagle-import") (part "R-TRIMM3296X"))
    )
    (comp (ref "R22")
      (value "100k")
      (footprint "eagle-import:RTRIM3296X")
      (libsource (lib "eagle-import") (part "R-TRIMM3296X"))
    )
    (comp (ref "R23")
      (value "100k")
      (footprint "eagle-import:RTRIM3296X")
      (libsource (lib "eagle-import") (part "R-TRIMM3296X"))
    )
    (comp (ref "R24")
      (value "100k")
      (footprint "eagle-import:RTRIM3296X")
      (libsource (lib "eagle-import") (part "R-TRIMM3296X"))
    )
    (comp (ref "R25")
      (value "100k")
      (footprint "eagle-import:RTRIM3296X")
      (libsource (lib "eagle-import") (part "R-TRIMM3296X"))
    )
    (comp (ref "R26")
      (value "10k")
      (footprint "eagle-import:0805")
      (libsource (lib "eagle-import") (part "RESISTOR0805-RES"))
    )
    (comp (ref "R27")
      (value "10k")
      (footprint "eagle-import:0805")
      (libsource (lib "eagle-import") (part "RESISTOR0805-RES"))
    )
    (comp (ref "R28")
      (value "10k")
      (footprint "eagle-import:0805")
      (libsource (lib "eagle-import") (part "RESISTOR0805-RES"))
    )
    (comp (ref "R29")
      (value "100k")
      (footprint "eagle-import:0805")
      (libsource (lib "eagle-import") (part "RESISTOR0805-RES"))
    )
    (comp (ref "R30")
      (value "100k")
      (footprint "eagle-import:0805")
      (libsource (lib "eagle-import") (part "RESISTOR0805-RES"))
    )
    (comp (ref "R31")
      (value "100k")
      (footprint "eagle-import:0805")
      (libsource (lib "eagle-import") (part "RESISTOR0805-RES"))
    )
    (comp (ref "R32")
      (value "10k")
      (footprint "eagle-import:0805")
      (libsource (lib "eagle-import") (part "RESISTOR0805-RES"))
    )
    (comp (ref "R33")
      (value "1k")
      (footprint "eagle-import:0805")
      (libsource (lib "eagle-import") (part "RESISTOR0805-RES"))
    )
    (comp (ref "R34")
      (value "100k")
      (footprint "eagle-import:RTRIM3296X")
      (libsource (lib "eagle-import") (part "R-TRIMM3296X"))
    )
    (comp (ref "R35")
      (value "100k")
      (footprint "eagle-import:RTRIM3296X")
      (libsource (lib "eagle-import") (part "R-TRIMM3296X"))
    )
    (comp (ref "R36")
      (value "10")
      (footprint "eagle-import:0805")
      (libsource (lib "eagle-import") (part "RESISTOR0805-RES"))
    )
    (comp (ref "R38")
      (value "100k")
      (footprint "eagle-import:RTRIM3296X")
      (libsource (lib "eagle-import") (part "R-TRIMM3296X"))
    )
  )
  (nets
    (net (code "1") (name "A5V") (class "Default")
      (node (ref "C25") (pin "1") (pinfunction "+_1") (pintype "passive"))
      (node (ref "C26") (pin "1") (pinfunction "1_1") (pintype "passive"))
      (node (ref "IC1") (pin "8") (pinfunction "V+_8") (pintype "power_in"))
      (node (ref "IC2") (pin "8") (pinfunction "V+_8") (pintype "power_in"))
      (node (ref "IC3") (pin "8") (pinfunction "V+_8") (pintype "power_in"))
      (node (ref "R26") (pin "1") (pinfunction "1_1") (pintype "passive"))
      (node (ref "R27") (pin "1") (pinfunction "1_1") (pintype "passive"))
      (node (ref "R36") (pin "2") (pinfunction "2_2") (pintype "passive"))
      (node (ref "R6") (pin "1") (pinfunction "1_1") (pintype "passive"))
      (node (ref "R7") (pin "1") (pinfunction "1_1") (pintype "passive"))
      (node (ref "R8") (pin "1") (pinfunction "1_1") (pintype "passive"))
      (node (ref "R9") (pin "1") (pinfunction "1_1") (pintype "passive"))
    )
    (net (code "2") (name "AUDIO_AMP") (class "Default")
      (node (ref "C1") (pin "1") (pinfunction "1_1") (pintype "passive"))
      (node (ref "JP7") (pin "2") (pinfunction "2_2") (pintype "passive"))
    )
    (net (code "3") (name "CH_A") (class "Default")
      (node (ref "C17") (pin "1") (pinfunction "1_1") (pintype "passive"))
      (node (ref "R22") (pin "2") (pinfunction "S_2") (pintype "passive"))
    )
    (net (code "4") (name "CH_B") (class "Default")
      (node (ref "C18") (pin "1") (pinfunction "1_1") (pintype "passive"))
      (node (ref "R23") (pin "2") (pinfunction "S_2") (pintype "passive"))
    )
    (net (code "5") (name "CH_C") (class "Default")
      (node (ref "C19") (pin "1") (pinfunction "1_1") (pintype "passive"))
      (node (ref "R24") (pin "2") (pinfunction "S_2") (pintype "passive"))
    )
    (net (code "6") (name "COS_AUDIO") (class "Default")
      (node (ref "JP1") (pin "5") (pinfunction "5_5") (pintype "passive"))
      (node (ref "R25") (pin "2") (pinfunction "S_2") (pintype "passive"))
    )
    (net (code "7") (name "CW_AUDIO") (class "Default")
      (node (ref "C27") (pin "1") (pinfunction "1_1") (pintype "passive"))
      (node (ref "C4") (pin "1") (pinfunction "1_1") (pintype "passive"))
      (node (ref "R41") (pin "1") (pinfunction "1_1") (pintype "passive"))
    )
    (net (code "8") (name "CW_TONE_OUT") (class "Default")
      (node (ref "JP2") (pin "10") (pinfunction "10_10") (pintype "passive"))
      (node (ref "R39") (pin "2") (pinfunction "2_2") (pintype "passive"))
    )
    (net (code "9") (name "ERASE") (class "Default")
      (node (ref "IC$1") (pin "4") (pinfunction "ERASE_4") (pintype "bidirectional"))
      (node (ref "JP1") (pin "13") (pinfunction "13_13") (pintype "passive"))
    )
    (net (code "10") (name "ERASE_IN") (class "Default")
      (node (ref "JP2") (pin "8") (pinfunction "8_8") (pintype "passive"))
      (node (ref "S4") (pin "1") (pinfunction "1_1") (pintype "passive"))
    )
    (net (code "11") (name "GND") (class "Default")
      (node (ref "C10") (pin "1") (pinfunction "1_1") (pintype "passive"))
      (node (ref "C11") (pin "1") (pinfunction "1_1") (pintype "passive"))
      (node (ref "C16") (pin "1") (pinfunction "1_1") (pintype "passive"))
      (node (ref "C2") (pin "1") (pinfunction "1_1") (pintype "passive"))
      (node (ref "C20") (pin "1") (pinfunction "1_1") (pintype "passive"))
      (node (ref "C22") (pin "2") (pinfunction "-_2") (pintype "passive"))
      (node (ref "C25") (pin "2") (pinfunction "-_2") (pintype "passive"))
      (node (ref "C26") (pin "2") (pinfunction "2_2") (pintype "passive"))
      (node (ref "C27") (pin "2") (pinfunction "2_2") (pintype "passive"))
      (node (ref "C28") (pin "-") (pinfunction "-_-") (pintype "passive"))
      (node (ref "C29") (pin "2") (pinfunction "2_2") (pintype "passive"))
      (node (ref "C31") (pin "2") (pinfunction "-_2") (pintype "passive"))
      (node (ref "C32") (pin "2") (pinfunction "2_2") (pintype "passive"))
      (node (ref "C34") (pin "1") (pinfunction "1_1") (pintype "passive"))
      (node (ref "C36") (pin "1") (pinfunction "1_1") (pintype "passive"))
      (node (ref "C37") (pin "1") (pinfunction "1_1") (pintype "passive"))
      (node (ref "C38") (pin "1") (pinfunction "1_1") (pintype "passive"))
      (node (ref "C39") (pin "1") (pinfunction "1_1") (pintype "passive"))
      (node (ref "C40") (pin "2") (pinfunction "2_2") (pintype "passive"))
      (node (ref "C6") (pin "1") (pinfunction "1_1") (pintype "passive"))
      (node (ref "C9") (pin "1") (pinfunction "1_1") (pintype "passive"))
      (node (ref "IC$1") (pin "25") (pinfunction "VSSA_25") (pintype "bidirectional"))
      (node (ref "IC$1") (pin "26") (pinfunction "VSSD_26") (pintype "bidirectional"))
      (node (ref "IC$1") (pin "27") (pinfunction "VSSP1_27") (pintype "bidirectional"))
      (node (ref "IC$1") (pin "28") (pinfunction "VSSP2_28") (pintype "bidirectional"))
      (node (ref "IC1") (pin "4") (pinfunction "V-_4") (pintype "power_in"))
      (node (ref "IC2") (pin "4") (pinfunction "V-_4") (pintype "power_in"))
      (node (ref "IC3") (pin "4") (pinfunction "V-_4") (pintype "power_in"))
      (node (ref "IC4") (pin "3") (pinfunction "GND_3") (pintype "passive"))
      (node (ref "JP1") (pin "1") (pinfunction "1_1") (pintype "passive"))
      (node (ref "JP3") (pin "2") (pinfunction "2_2") (pintype "passive"))
      (node (ref "JP4") (pin "2") (pinfunction "2_2") (pintype "passive"))
      (node (ref "JP5") (pin "8") (pinfunction "8_8") (pintype "passive"))
      (node (ref "JP7") (pin "3") (pinfunction "3_3") (pintype "passive"))
      (node (ref "LED1") (pin "A") (pinfunction "A_A") (pintype "passive"))
      (node (ref "LED2") (pin "A") (pinfunction "A_A") (pintype "passive"))
      (node (ref "LED3") (pin "A") (pinfunction "A_A") (pintype "passive"))
      (node (ref "LED4") (pin "A") (pinfunction "A_A") (pintype "passive"))
      (node (ref "LED5") (pin "A") (pinfunction "A_A") (pintype "passive"))
      (node (ref "LED6") (pin "A") (pinfunction "A_A") (pintype "passive"))
      (node (ref "LED7") (pin "A") (pinfunction "A_A") (pintype "passive"))
      (node (ref "MODE_SW") (pin "2") (pinfunction "2_2") (pintype "passive"))
      (node (ref "Q3") (pin "C") (pinfunction "C_C") (pintype "passive"))
      (node (ref "R12") (pin "1") (pinfunction "1_1") (pintype "passive"))
      (node (ref "R15") (pin "1") (pinfunction "1_1") (pintype "passive"))
      (node (ref "R16") (pin "1") (pinfunction "1_1") (pintype "passive"))
      (node (ref "R17") (pin "1") (pinfunction "1_1") (pintype "passive"))
      (node (ref "R22") (pin "1") (pinfunction "A_1") (pintype "passive"))
      (node (ref "R23") (pin "1") (pinfunction "A_1") (pintype "passive"))
      (node (ref "R24") (pin "1") (pinfunction "A_1") (pintype "passive"))
      (node (ref "R25") (pin "1") (pinfunction "A_1") (pintype "passive"))
      (node (ref "R28") (pin "1") (pinfunction "1_1") (pintype "passive"))
      (node (ref "R32") (pin "1") (pinfunction "1_1") (pintype "passive"))
      (node (ref "R38") (pin "1") (pinfunction "A_1") (pintype "passive"))
      (node (ref "R40") (pin "1") (pinfunction "1_1") (pintype "passive"))
      (node (ref "R49") (pin "1") (pinfunction "1_1") (pintype "passive"))
      (node (ref "R5") (pin "1") (pinfunction "1_1") (pintype "passive"))
      (node (ref "R53") (pin "1") (pinfunction "1_1") (pintype "passive"))
      (node (ref "S1") (pin "3") (pinfunction "2_3") (pintype "passive"))
      (node (ref "S2") (pin "3") (pinfunction "2_3") (pintype "passive"))
      (node (ref "S3") (pin "3") (pinfunction "2_3") (pintype "passive"))
      (node (ref "S4") (pin "3") (pinfunction "2_3") (pintype "passive"))
      (node (ref "S5") (pin "3") (pinfunction "2_3") (pintype "passive"))
    )
    (net (code "12") (name "LED_COS") (class "Default")
      (node (ref "JP2") (pin "4") (pinfunction "4_4") (pintype "passive"))
      (node (ref "R45") (pin "1") (pinfunction "1_1") (pintype "passive"))
    )
    (net (code "13") (name "LED_CWID") (class "Default")
      (node (ref "JP2") (pin "3") (pinfunction "3_3") (pintype "passive"))
      (node (ref "R46") (pin "1") (pinfunction "1_1") (pintype "passive"))
    )
    (net (code "14") (name "LED_HEARTBEAT") (class "Default")
      (node (ref "JP2") (pin "6") (pinfunction "6_6") (pintype "passive"))
      (node (ref "R43") (pin "1") (pinfunction "1_1") (pintype "passive"))
    )
    (net (code "15") (name "LED_INIT") (class "Default")
      (node (ref "JP1") (pin "3") (pinfunction "3_3") (pintype "passive"))
      (node (ref "R42") (pin "1") (pinfunction "1_1") (pintype "passive"))
    )
    (net (code "16") (name "LED_PTT") (class "Default")
      (node (ref "JP2") (pin "5") (pinfunction "5_5") (pintype "passive"))
      (node (ref "R44") (pin "1") (pinfunction "1_1") (pintype "passive"))
    )
    (net (code "17") (name "LED_RECORDING") (class "Default")
      (node (ref "JP2") (pin "1") (pinfunction "1_1") (pintype "passive"))
      (node (ref "R48") (pin "1") (pinfunction "1_1") (pintype "passive"))
    )
    (net (code "18") (name "LED_VOICEID") (class "Default")
      (node (ref "JP2") (pin "2") (pinfunction "2_2") (pintype "passive"))
      (node (ref "R47") (pin "1") (pinfunction "1_1") (pintype "passive"))
    )
    (net (code "19") (name "MIC_AUDIO_IN") (class "Default")
      (node (ref "C5") (pin "1") (pinfunction "1_1") (pintype "passive"))
      (node (ref "JP5") (pin "6") (pinfunction "6_6") (pintype "passive"))
    )
    (net (code "20") (name "MIC_PTT_IN") (class "Default")
      (node (ref "JP1") (pin "7") (pinfunction "7_7") (pintype "passive"))
      (node (ref "JP5") (pin "4") (pinfunction "4_4") (pintype "passive"))
    )
    (net (code "21") (name "MODE_IN") (class "Default")
      (node (ref "JP1") (pin "2") (pinfunction "2_2") (pintype "passive"))
      (node (ref "MODE_SW") (pin "1") (pinfunction "1_1") (pintype "passive"))
    )
    (net (code "22") (name "Net-(C1-Pad2)") (class "Default")
      (node (ref "C1") (pin "2") (pinfunction "2_2") (pintype "passive"))
      (node (ref "R2") (pin "2") (pinfunction "2_2") (pintype "passive"))
    )
    (net (code "23") (name "Net-(C4-Pad2)") (class "Default")
      (node (ref "C4") (pin "2") (pinfunction "2_2") (pintype "passive"))
      (node (ref "R10") (pin "1") (pinfunction "1_1") (pintype "passive"))
    )
    (net (code "24") (name "Net-(C5-Pad2)") (class "Default")
      (node (ref "C5") (pin "2") (pinfunction "2_2") (pintype "passive"))
      (node (ref "R11") (pin "1") (pinfunction "1_1") (pintype "passive"))
    )
    (net (code "25") (name "Net-(C7-Pad2)") (class "Default")
      (node (ref "C7") (pin "2") (pinfunction "2_2") (pintype "passive"))
      (node (ref "R13") (pin "1") (pinfunction "1_1") (pintype "passive"))
    )
    (net (code "26") (name "Net-(C8-Pad2)") (class "Default")
      (node (ref "C8") (pin "2") (pinfunction "2_2") (pintype "passive"))
      (node (ref "R14") (pin "1") (pinfunction "1_1") (pintype "passive"))
    )
    (net (code "27") (name "Net-(C17-Pad2)") (class "Default")
      (node (ref "C17") (pin "2") (pinfunction "2_2") (pintype "passive"))
      (node (ref "R29") (pin "1") (pinfunction "1_1") (pintype "passive"))
    )
    (net (code "28") (name "Net-(C18-Pad2)") (class "Default")
      (node (ref "C18") (pin "2") (pinfunction "2_2") (pintype "passive"))
      (node (ref "R30") (pin "1") (pinfunction "1_1") (pintype "passive"))
    )
    (net (code "29") (name "Net-(C19-Pad2)") (class "Default")
      (node (ref "C19") (pin "2") (pinfunction "2_2") (pintype "passive"))
      (node (ref "R31") (pin "1") (pinfunction "1_1") (pintype "passive"))
    )
    (net (code "30") (name "Net-(C21-Pad2)") (class "Default")
      (node (ref "C21") (pin "2") (pinfunction "2_2") (pintype "passive"))
      (node (ref "R33") (pin "1") (pinfunction "1_1") (pintype "passive"))
    )
    (net (code "31") (name "Net-(C30-Pad2)") (class "Default")
      (node (ref "C30") (pin "2") (pinfunction "2_2") (pintype "passive"))
      (node (ref "JP5") (pin "7") (pinfunction "7_7") (pintype "passive"))
    )
    (net (code "32") (name "Net-(C35-Pad1)") (class "Default")
      (node (ref "C35") (pin "1") (pinfunction "1_1") (pintype "passive"))
      (node (ref "R52") (pin "2") (pinfunction "2_2") (pintype "passive"))
    )
    (net (code "33") (name "Net-(D1-PadC)") (class "Default")
      (node (ref "D1") (pin "C") (pinfunction "C_C") (pintype "passive"))
      (node (ref "D2") (pin "A") (pinfunction "A_A") (pintype "passive"))
    )
    (net (code "34") (name "Net-(IC$1-AGC)") (class "Default")
      (node (ref "C34") (pin "2") (pinfunction "2_2") (pintype "passive"))
      (node (ref "IC$1") (pin "1") (pinfunction "AGC_1") (pintype "bidirectional"))
    )
    (net (code "35") (name "Net-(IC$1-ANAIN)") (class "Default")
      (node (ref "C33") (pin "2") (pinfunction "2_2") (pintype "passive"))
      (node (ref "IC$1") (pin "2") (pinfunction "ANAIN_2") (pintype "bidirectional"))
    )
    (net (code "36") (name "Net-(IC$1-AUD{slash}AUX)") (class "Default")
      (node (ref "C35") (pin "2") (pinfunction "2_2") (pintype "passive"))
      (node (ref "IC$1") (pin "3") (pinfunction "AUD/AUX_3") (pintype "bidirectional"))
    )
    (net (code "37") (name "Net-(IC$1-INT{slash}RDY)") (class "Default")
      (node (ref "IC$1") (pin "7") (pinfunction "INT/RDY_7") (pintype "bidirectional"))
      (node (ref "R51") (pin "1") (pinfunction "1_1") (pintype "passive"))
    )
    (net (code "38") (name "Net-(IC$1-LED)") (class "Default")
      (node (ref "IC$1") (pin "8") (pinfunction "LED_8") (pintype "bidirectional"))
      (node (ref "R54") (pin "1") (pinfunction "1_1") (pintype "passive"))
    )
    (net (code "39") (name "Net-(IC$1-ROSC)") (class "Default")
      (node (ref "IC$1") (pin "16") (pinfunction "ROSC_16") (pintype "bidirectional"))
      (node (ref "R49") (pin "2") (pinfunction "2_2") (pintype "passive"))
    )
    (net (code "40") (name "Net-(IC1A-+IN)") (class "Default")
      (node (ref "C9") (pin "2") (pinfunction "2_2") (pintype "passive"))
      (node (ref "IC1") (pin "3") (pinfunction "+IN_3") (pintype "input"))
      (node (ref "R15") (pin "2") (pinfunction "2_2") (pintype "passive"))
      (node (ref "R7") (pin "2") (pinfunction "2_2") (pintype "passive"))
    )
    (net (code "41") (name "Net-(IC1A--IN)") (class "Default")
      (node (ref "IC1") (pin "2") (pinfunction "-IN_2") (pintype "input"))
      (node (ref "R11") (pin "2") (pinfunction "2_2") (pintype "passive"))
      (node (ref "R18") (pin "3") (pinfunction "E_3") (pintype "passive"))
    )
    (net (code "42") (name "Net-(IC1A-OUT)") (class "Default")
      (node (ref "C12") (pin "1") (pinfunction "1_1") (pintype "passive"))
      (node (ref "IC1") (pin "1") (pinfunction "OUT_1") (pintype "output"))
      (node (ref "R18") (pin "1") (pinfunction "A_1") (pintype "passive"))
      (node (ref "R18") (pin "2") (pinfunction "S_2") (pintype "passive"))
    )
    (net (code "43") (name "Net-(IC1B-+IN)") (class "Default")
      (node (ref "C6") (pin "2") (pinfunction "2_2") (pintype "passive"))
      (node (ref "IC1") (pin "5") (pinfunction "+IN_5") (pintype "input"))
      (node (ref "R12") (pin "2") (pinfunction "2_2") (pintype "passive"))
      (node (ref "R6") (pin "2") (pinfunction "2_2") (pintype "passive"))
    )
    (net (code "44") (name "Net-(IC1B--IN)") (class "Default")
      (node (ref "IC1") (pin "6") (pinfunction "-IN_6") (pintype "input"))
      (node (ref "R10") (pin "2") (pinfunction "2_2") (pintype "passive"))
      (node (ref "R19") (pin "3") (pinfunction "E_3") (pintype "passive"))
    )
    (net (code "45") (name "Net-(IC1B-OUT)") (class "Default")
      (node (ref "C13") (pin "1") (pinfunction "1_1") (pintype "passive"))
      (node (ref "IC1") (pin "7") (pinfunction "OUT_7") (pintype "output"))
      (node (ref "R19") (pin "1") (pinfunction "A_1") (pintype "passive"))
      (node (ref "R19") (pin "2") (pinfunction "S_2") (pintype "passive"))
    )
    (net (code "46") (name "Net-(IC2A-+IN)") (class "Default")
      (node (ref "C10") (pin "2") (pinfunction "2_2") (pintype "passive"))
      (node (ref "IC2") (pin "3") (pinfunction "+IN_3") (pintype "input"))
      (node (ref "R16") (pin "2") (pinfunction "2_2") (pintype "passive"))
      (node (ref "R8") (pin "2") (pinfunction "2_2") (pintype "passive"))
    )
    (net (code "47") (name "Net-(IC2A--IN)") (class "Default")
      (node (ref "IC2") (pin "2") (pinfunction "-IN_2") (pintype "input"))
      (node (ref "R13") (pin "2") (pinfunction "2_2") (pintype "passive"))
      (node (ref "R20") (pin "3") (pinfunction "E_3") (pintype "passive"))
    )
    (net (code "48") (name "Net-(IC2A-OUT)") (class "Default")
      (node (ref "C14") (pin "1") (pinfunction "1_1") (pintype "passive"))
      (node (ref "IC2") (pin "1") (pinfunction "OUT_1") (pintype "output"))
      (node (ref "R20") (pin "1") (pinfunction "A_1") (pintype "passive"))
      (node (ref "R20") (pin "2") (pinfunction "S_2") (pintype "passive"))
    )
    (net (code "49") (name "Net-(IC2B-+IN)") (class "Default")
      (node (ref "C20") (pin "2") (pinfunction "2_2") (pintype "passive"))
      (node (ref "IC2") (pin "5") (pinfunction "+IN_5") (pintype "input"))
      (node (ref "R27") (pin "2") (pinfunction "2_2") (pintype "passive"))
      (node (ref "R32") (pin "2") (pinfunction "2_2") (pintype "passive"))
    )
    (net (code "50") (name "Net-(IC2B--IN)") (class "Default")
      (node (ref "IC2") (pin "6") (pinfunction "-IN_6") (pintype "input"))
      (node (ref "R29") (pin "2") (pinfunction "2_2") (pintype "passive"))
      (node (ref "R30") (pin "2") (pinfunction "2_2") (pintype "passive"))
      (node (ref "R31") (pin "2") (pinfunction "2_2") (pintype "passive"))
      (node (ref "R34") (pin "3") (pinfunction "E_3") (pintype "passive"))
    )
    (net (code "51") (name "Net-(IC2B-OUT)") (class "Default")
      (node (ref "C24") (pin "1") (pinfunction "1_1") (pintype "passive"))
      (node (ref "IC2") (pin "7") (pinfunction "OUT_7") (pintype "output"))
      (node (ref "R34") (pin "1") (pinfunction "A_1") (pintype "passive"))
      (node (ref "R34") (pin "2") (pinfunction "S_2") (pintype "passive"))
    )
    (net (code "52") (name "Net-(IC3A-+IN)") (class "Default")
      (node (ref "C11") (pin "2") (pinfunction "2_2") (pintype "passive"))
      (node (ref "IC3") (pin "3") (pinfunction "+IN_3") (pintype "input"))
      (node (ref "R17") (pin "2") (pinfunction "2_2") (pintype "passive"))
      (node (ref "R9") (pin "2") (pinfunction "2_2") (pintype "passive"))
    )
    (net (code "53") (name "Net-(IC3A--IN)") (class "Default")
      (node (ref "IC3") (pin "2") (pinfunction "-IN_2") (pintype "input"))
      (node (ref "R14") (pin "2") (pinfunction "2_2") (pintype "passive"))
      (node (ref "R21") (pin "3") (pinfunction "E_3") (pintype "passive"))
    )
    (net (code "54") (name "Net-(IC3A-OUT)") (class "Default")
      (node (ref "C15") (pin "1") (pinfunction "1_1") (pintype "passive"))
      (node (ref "IC3") (pin "1") (pinfunction "OUT_1") (pintype "output"))
      (node (ref "R21") (pin "1") (pinfunction "A_1") (pintype "passive"))
      (node (ref "R21") (pin "2") (pinfunction "S_2") (pintype "passive"))
    )
    (net (code "55") (name "Net-(IC3B-+IN)") (class "Default")
      (node (ref "C16") (pin "2") (pinfunction "2_2") (pintype "passive"))
      (node (ref "IC3") (pin "5") (pinfunction "+IN_5") (pintype "input"))
      (node (ref "R26") (pin "2") (pinfunction "2_2") (pintype "passive"))
      (node (ref "R28") (pin "2") (pinfunction "2_2") (pintype "passive"))
    )
    (net (code "56") (name "Net-(IC3B--IN)") (class "Default")
      (node (ref "IC3") (pin "6") (pinfunction "-IN_6") (pintype "input"))
      (node (ref "R33") (pin "2") (pinfunction "2_2") (pintype "passive"))
      (node (ref "R35") (pin "3") (pinfunction "E_3") (pintype "passive"))
    )
    (net (code "57") (name "Net-(IC3B-OUT)") (class "Default")
      (node (ref "C23") (pin "1") (pinfunction "1_1") (pintype "passive"))
      (node (ref "IC3") (pin "7") (pinfunction "OUT_7") (pintype "output"))
      (node (ref "R35") (pin "1") (pinfunction "A_1") (pintype "passive"))
      (node (ref "R35") (pin "2") (pinfunction "S_2") (pintype "passive"))
    )
    (net (code "58") (name "Net-(LED1-C)") (class "Default")
      (node (ref "LED1") (pin "K") (pinfunction "C_K") (pintype "passive"))
      (node (ref "R42") (pin "2") (pinfunction "2_2") (pintype "passive"))
    )
    (net (code "59") (name "Net-(LED2-C)") (class "Default")
      (node (ref "LED2") (pin "K") (pinfunction "C_K") (pintype "passive"))
      (node (ref "R43") (pin "2") (pinfunction "2_2") (pintype "passive"))
    )
    (net (code "60") (name "Net-(LED3-C)") (class "Default")
      (node (ref "LED3") (pin "K") (pinfunction "C_K") (pintype "passive"))
      (node (ref "R44") (pin "2") (pinfunction "2_2") (pintype "passive"))
    )
    (net (code "61") (name "Net-(LED4-C)") (class "Default")
      (node (ref "LED4") (pin "K") (pinfunction "C_K") (pintype "passive"))
      (node (ref "R45") (pin "2") (pinfunction "2_2") (pintype "passive"))
    )
    (net (code "62") (name "Net-(LED5-C)") (class "Default")
      (node (ref "LED5") (pin "K") (pinfunction "C_K") (pintype "passive"))
      (node (ref "R46") (pin "2") (pinfunction "2_2") (pintype "passive"))
    )
    (net (code "63") (name "Net-(LED6-C)") (class "Default")
      (node (ref "LED6") (pin "K") (pinfunction "C_K") (pintype "passive"))
      (node (ref "R47") (pin "2") (pinfunction "2_2") (pintype "passive"))
    )
    (net (code "64") (name "Net-(LED7-C)") (class "Default")
      (node (ref "LED7") (pin "K") (pinfunction "C_K") (pintype "passive"))
      (node (ref "R48") (pin "2") (pinfunction "2_2") (pintype "passive"))
    )
    (net (code "65") (name "Net-(LED8-PadC)") (class "Default")
      (node (ref "LED8") (pin "C") (pinfunction "C_C") (pintype "passive"))
      (node (ref "R54") (pin "2") (pinfunction "2_2") (pintype "passive"))
    )
    (net (code "66") (name "Net-(Q1-B)") (class "Default")
      (node (ref "Q1") (pin "2") (pinfunction "B_2") (pintype "passive"))
      (node (ref "R2") (pin "1") (pinfunction "1_1") (pintype "passive"))
      (node (ref "R3") (pin "2") (pinfunction "2_2") (pintype "passive"))
    )
    (net (code "67") (name "Net-(Q1-C)") (class "Default")
      (node (ref "D2") (pin "C") (pinfunction "C_C") (pintype "passive"))
      (node (ref "Q1") (pin "3") (pinfunction "C_3") (pintype "passive"))
      (node (ref "Q3") (pin "B") (pinfunction "B_B") (pintype "passive"))
    )
    (net (code "68") (name "Net-(Q1-E)") (class "Default")
      (node (ref "C2") (pin "2") (pinfunction "2_2") (pintype "passive"))
      (node (ref "Q1") (pin "1") (pinfunction "E_1") (pintype "passive"))
      (node (ref "R5") (pin "2") (pinfunction "2_2") (pintype "passive"))
    )
    (net (code "69") (name "Net-(Q2-B)") (class "Default")
      (node (ref "D1") (pin "A") (pinfunction "A_A") (pintype "passive"))
      (node (ref "Q2") (pin "2") (pinfunction "B_2") (pintype "passive"))
      (node (ref "R4") (pin "2") (pinfunction "2_2") (pintype "passive"))
    )
    (net (code "70") (name "Net-(Q2-C)") (class "Default")
      (node (ref "Q2") (pin "3") (pinfunction "C_3") (pintype "passive"))
      (node (ref "R1") (pin "1") (pinfunction "1_1") (pintype "passive"))
      (node (ref "R4") (pin "1") (pinfunction "1_1") (pintype "passive"))
    )
    (net (code "71") (name "Net-(Q2-E)") (class "Default")
      (node (ref "C3") (pin "1") (pinfunction "1_1") (pintype "passive"))
      (node (ref "Q2") (pin "1") (pinfunction "E_1") (pintype "passive"))
      (node (ref "Q3") (pin "E") (pinfunction "E_E") (pintype "passive"))
      (node (ref "R3") (pin "1") (pinfunction "1_1") (pintype "passive"))
    )
    (net (code "72") (name "Net-(R22-E)") (class "Default")
      (node (ref "C12") (pin "2") (pinfunction "2_2") (pintype "passive"))
      (node (ref "R22") (pin "3") (pinfunction "E_3") (pintype "passive"))
    )
    (net (code "73") (name "Net-(R23-E)") (class "Default")
      (node (ref "C13") (pin "2") (pinfunction "2_2") (pintype "passive"))
      (node (ref "R23") (pin "3") (pinfunction "E_3") (pintype "passive"))
    )
    (net (code "74") (name "Net-(R24-E)") (class "Default")
      (node (ref "C14") (pin "2") (pinfunction "2_2") (pintype "passive"))
      (node (ref "R24") (pin "3") (pinfunction "E_3") (pintype "passive"))
    )
    (net (code "75") (name "Net-(R25-E)") (class "Default")
      (node (ref "C15") (pin "2") (pinfunction "2_2") (pintype "passive"))
      (node (ref "R25") (pin "3") (pinfunction "E_3") (pintype "passive"))
    )
    (net (code "76") (name "Net-(R38-E)") (class "Default")
      (node (ref "C24") (pin "2") (pinfunction "2_2") (pintype "passive"))
      (node (ref "R38") (pin "3") (pinfunction "E_3") (pintype "passive"))
    )
    (net (code "77") (name "Net-(R39-Pad1)") (class "Default")
      (node (ref "R39") (pin "1") (pinfunction "1_1") (pintype "passive"))
      (node (ref "R40") (pin "2") (pinfunction "2_2") (pintype "passive"))
      (node (ref "R41") (pin "2") (pinfunction "2_2") (pintype "passive"))
    )
    (net (code "78") (name "PLAY") (class "Default")
      (node (ref "IC$1") (pin "13") (pinfunction "PLAY_13") (pintype "bidirectional"))
      (node (ref "JP1") (pin "12") (pinfunction "12_12") (pintype "passive"))
    )
    (net (code "79") (name "PLAY_CWID_IN") (class "Default")
      (node (ref "JP2") (pin "11") (pinfunction "11_11") (pintype "passive"))
      (node (ref "S2") (pin "1") (pinfunction "1_1") (pintype "passive"))
    )
    (net (code "80") (name "PLAY_VOICEID_IN") (class "Default")
      (node (ref "JP2") (pin "9") (pinfunction "9_9") (pintype "passive"))
      (node (ref "S1") (pin "1") (pinfunction "1_1") (pintype "passive"))
    )
    (net (code "81") (name "PREAMP_OUT") (class "Default")
      (node (ref "C23") (pin "2") (pinfunction "2_2") (pintype "passive"))
      (node (ref "JP7") (pin "1") (pinfunction "1_1") (pintype "passive"))
    )
    (net (code "82") (name "RECORD") (class "Default")
      (node (ref "IC$1") (pin "14") (pinfunction "REC_14") (pintype "bidirectional"))
      (node (ref "JP1") (pin "14") (pinfunction "14_14") (pintype "passive"))
    )
    (net (code "83") (name "RECORD_IN") (class "Default")
      (node (ref "JP2") (pin "7") (pinfunction "7_7") (pintype "passive"))
      (node (ref "S3") (pin "1") (pinfunction "1_1") (pintype "passive"))
    )
    (net (code "84") (name "REC_AUDIO_IN") (class "Default")
      (node (ref "C33") (pin "1") (pinfunction "1_1") (pintype "passive"))
      (node (ref "JP6") (pin "2") (pinfunction "2_2") (pintype "passive"))
    )
    (net (code "85") (name "RESET") (class "Default")
      (node (ref "IC$1") (pin "15") (pinfunction "RESET_15") (pintype "bidirectional"))
      (node (ref "R50") (pin "1") (pinfunction "1_1") (pintype "passive"))
    )
    (net (code "86") (name "RPTR_AUDIO_IN") (class "Default")
      (node (ref "C21") (pin "1") (pinfunction "1_1") (pintype "passive"))
      (node (ref "C8") (pin "1") (pinfunction "1_1") (pintype "passive"))
      (node (ref "JP5") (pin "1") (pinfunction "1_1") (pintype "passive"))
      (node (ref "JP6") (pin "3") (pinfunction "3_3") (pintype "passive"))
    )
    (net (code "87") (name "RPTR_MIC") (class "Default")
      (node (ref "C30") (pin "1") (pinfunction "1_1") (pintype "passive"))
      (node (ref "JP6") (pin "1") (pinfunction "1_1") (pintype "passive"))
      (node (ref "R38") (pin "2") (pinfunction "S_2") (pintype "passive"))
    )
    (net (code "88") (name "RPTR_MONITOR") (class "Default")
      (node (ref "JP1") (pin "8") (pinfunction "8_8") (pintype "passive"))
      (node (ref "JP5") (pin "5") (pinfunction "5_5") (pintype "passive"))
    )
    (net (code "89") (name "RPTR_PTT") (class "Default")
      (node (ref "JP1") (pin "6") (pinfunction "6_6") (pintype "passive"))
      (node (ref "JP5") (pin "3") (pinfunction "3_3") (pintype "passive"))
    )
    (net (code "90") (name "SPEAKER") (class "Default")
      (node (ref "C3") (pin "2") (pinfunction "2_2") (pintype "passive"))
      (node (ref "JP3") (pin "1") (pinfunction "1_1") (pintype "passive"))
    )
    (net (code "91") (name "VCC_12V") (class "Default")
      (node (ref "C28") (pin "+") (pinfunction "+_+") (pintype "passive"))
      (node (ref "C29") (pin "1") (pinfunction "1_1") (pintype "passive"))
      (node (ref "IC4") (pin "1") (pinfunction "VI_1") (pintype "input"))
      (node (ref "JP4") (pin "1") (pinfunction "1_1") (pintype "passive"))
      (node (ref "R1") (pin "2") (pinfunction "2_2") (pintype "passive"))
    )
    (net (code "92") (name "VDD_5V") (class "Default")
      (node (ref "C22") (pin "1") (pinfunction "+_1") (pintype "passive"))
      (node (ref "C31") (pin "1") (pinfunction "+_1") (pintype "passive"))
      (node (ref "C32") (pin "1") (pinfunction "1_1") (pintype "passive"))
      (node (ref "C36") (pin "2") (pinfunction "2_2") (pintype "passive"))
      (node (ref "C37") (pin "2") (pinfunction "2_2") (pintype "passive"))
      (node (ref "C38") (pin "2") (pinfunction "2_2") (pintype "passive"))
      (node (ref "C39") (pin "2") (pinfunction "2_2") (pintype "passive"))
      (node (ref "C40") (pin "1") (pinfunction "1_1") (pintype "passive"))
      (node (ref "IC$1") (pin "21") (pinfunction "VCCA_21") (pintype "bidirectional"))
      (node (ref "IC$1") (pin "22") (pinfunction "VCCD_22") (pintype "bidirectional"))
      (node (ref "IC$1") (pin "23") (pinfunction "VCCP_23") (pintype "bidirectional"))
      (node (ref "IC4") (pin "2") (pinfunction "VO_2") (pintype "passive"))
      (node (ref "JP2") (pin "14") (pinfunction "14_14") (pintype "passive"))
      (node (ref "LED8") (pin "A") (pinfunction "A_A") (pintype "passive"))
      (node (ref "R36") (pin "1") (pinfunction "1_1") (pintype "passive"))
      (node (ref "R50") (pin "2") (pinfunction "2_2") (pintype "passive"))
      (node (ref "R51") (pin "2") (pinfunction "2_2") (pintype "passive"))
    )
    (net (code "93") (name "VOICEID_AUDIO") (class "Default")
      (node (ref "C7") (pin "1") (pinfunction "1_1") (pintype "passive"))
      (node (ref "R52") (pin "1") (pinfunction "1_1") (pintype "passive"))
      (node (ref "R53") (pin "2") (pinfunction "2_2") (pintype "passive"))
    )
    (net (code "94") (name "VOLUME") (class "Default")
      (node (ref "IC$1") (pin "24") (pinfunction "VOL_24") (pintype "bidirectional"))
      (node (ref "S5") (pin "1") (pinfunction "1_1") (pintype "passive"))
    )
    (net (code "95") (name "unconnected-(IC$1-FT-Pad5)") (class "Default")
      (node (ref "IC$1") (pin "5") (pinfunction "FT_5") (pintype "bidirectional"))
    )
    (net (code "96") (name "unconnected-(IC$1-FWD-Pad6)") (class "Default")
      (node (ref "IC$1") (pin "6") (pinfunction "FWD_6") (pintype "bidirectional"))
    )
    (net (code "97") (name "unconnected-(IC$1-MIC+-Pad9)") (class "Default")
      (node (ref "IC$1") (pin "9") (pinfunction "MIC+_9") (pintype "bidirectional"))
    )
    (net (code "98") (name "unconnected-(IC$1-MIC--Pad10)") (class "Default")
      (node (ref "IC$1") (pin "10") (pinfunction "MIC-_10") (pintype "bidirectional"))
    )
    (net (code "99") (name "unconnected-(IC$1-MISO-Pad11)") (class "Default")
      (node (ref "IC$1") (pin "11") (pinfunction "MISO_11") (pintype "bidirectional"))
    )
    (net (code "100") (name "unconnected-(IC$1-MOSI-Pad12)") (class "Default")
      (node (ref "IC$1") (pin "12") (pinfunction "MOSI_12") (pintype "bidirectional"))
    )
    (net (code "101") (name "unconnected-(IC$1-SCLK-Pad17)") (class "Default")
      (node (ref "IC$1") (pin "17") (pinfunction "SCLK_17") (pintype "bidirectional"))
    )
    (net (code "102") (name "unconnected-(IC$1-SP+-Pad18)") (class "Default")
      (node (ref "IC$1") (pin "18") (pinfunction "SP+_18") (pintype "bidirectional"))
    )
    (net (code "103") (name "unconnected-(IC$1-SP--Pad19)") (class "Default")
      (node (ref "IC$1") (pin "19") (pinfunction "SP-_19") (pintype "bidirectional"))
    )
    (net (code "104") (name "unconnected-(IC$1-SS-Pad20)") (class "Default")
      (node (ref "IC$1") (pin "20") (pinfunction "SS_20") (pintype "bidirectional"))
    )
    (net (code "105") (name "unconnected-(JP1-Pad4)") (class "Default")
      (node (ref "JP1") (pin "4") (pinfunction "4_4") (pintype "passive"))
    )
    (net (code "106") (name "unconnected-(JP1-Pad9)") (class "Default")
      (node (ref "JP1") (pin "9") (pinfunction "9_9") (pintype "passive"))
    )
    (net (code "107") (name "unconnected-(JP1-Pad10)") (class "Default")
      (node (ref "JP1") (pin "10") (pinfunction "10_10") (pintype "passive"))
    )
    (net (code "108") (name "unconnected-(JP1-Pad11)") (class "Default")
      (node (ref "JP1") (pin "11") (pinfunction "11_11") (pintype "passive"))
    )
    (net (code "109") (name "unconnected-(JP2-Pad12)") (class "Default")
      (node (ref "JP2") (pin "12") (pinfunction "12_12") (pintype "passive"))
    )
    (net (code "110") (name "unconnected-(JP2-Pad13)") (class "Default")
      (node (ref "JP2") (pin "13") (pinfunction "13_13") (pintype "passive"))
    )
    (net (code "111") (name "unconnected-(JP5-Pad2)") (class "Default")
      (node (ref "JP5") (pin "2") (pinfunction "2_2") (pintype "passive"))
    )
  )
)
